# EPS.net
KiCad netlist of a schematic drawn in EAGLE
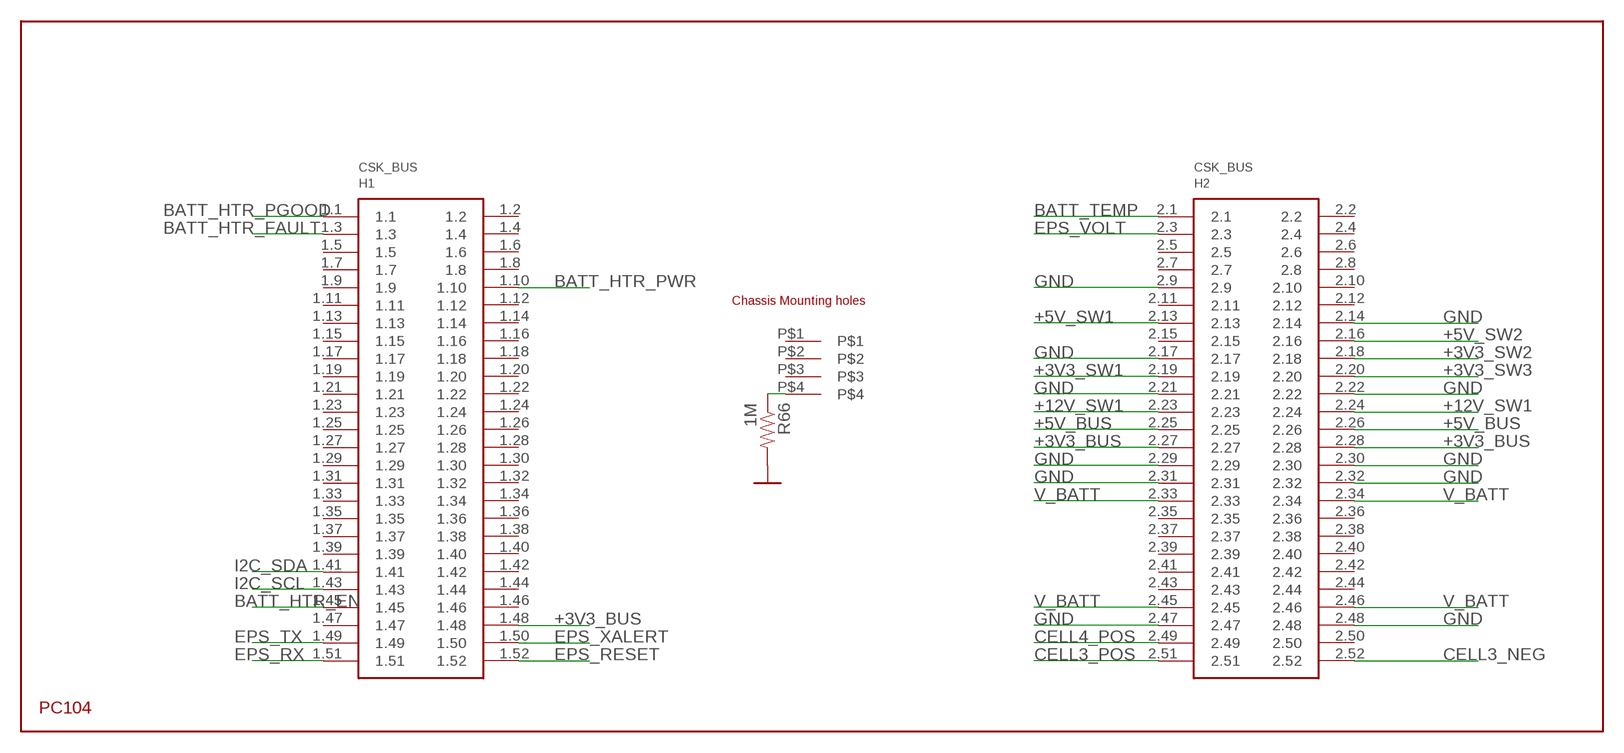
[diagram p0: schematic, sheet 1]
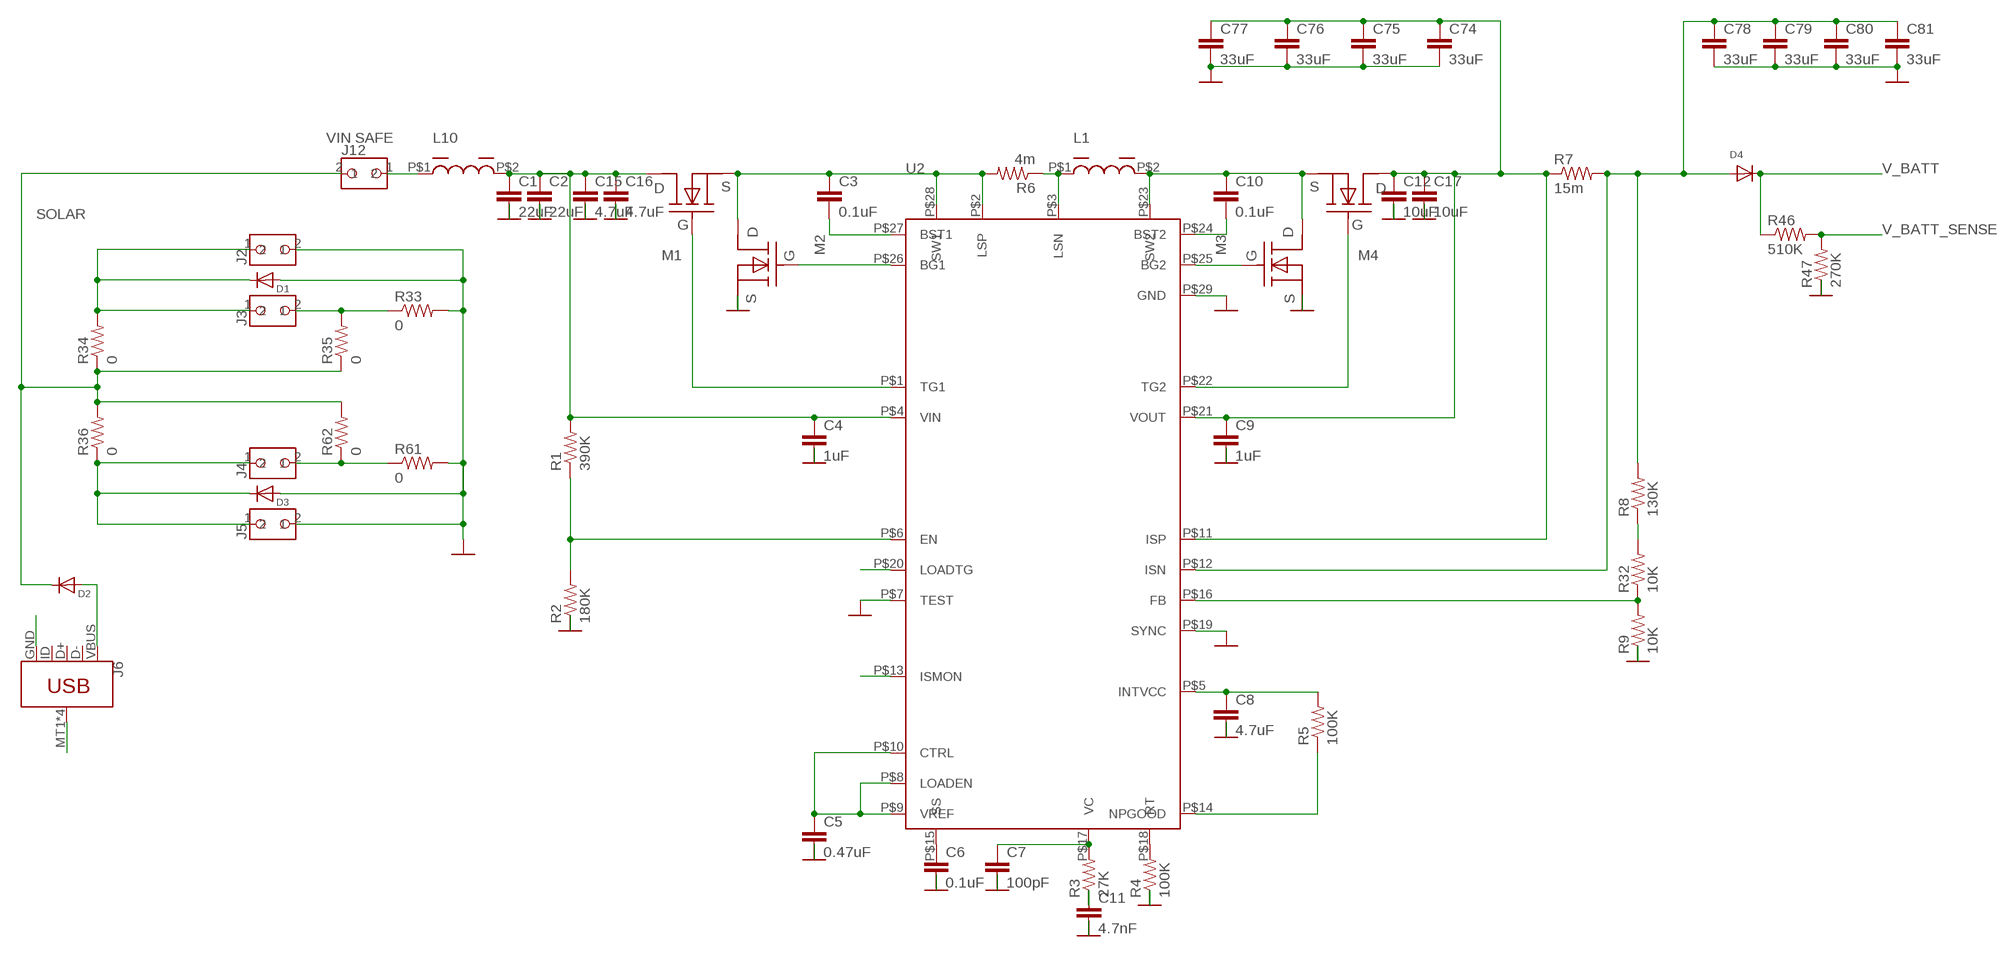
[diagram p1: schematic, sheet 2]
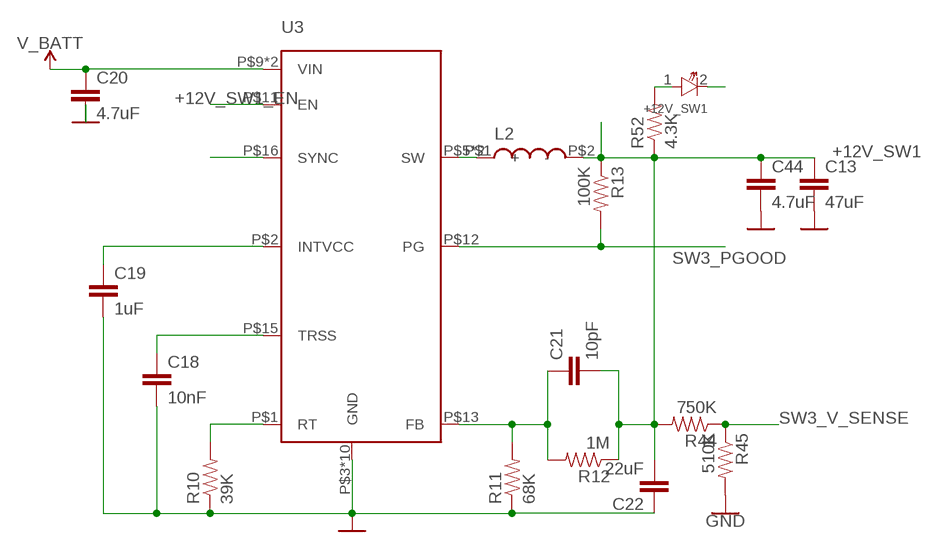
[diagram p2: schematic, sheet 3]
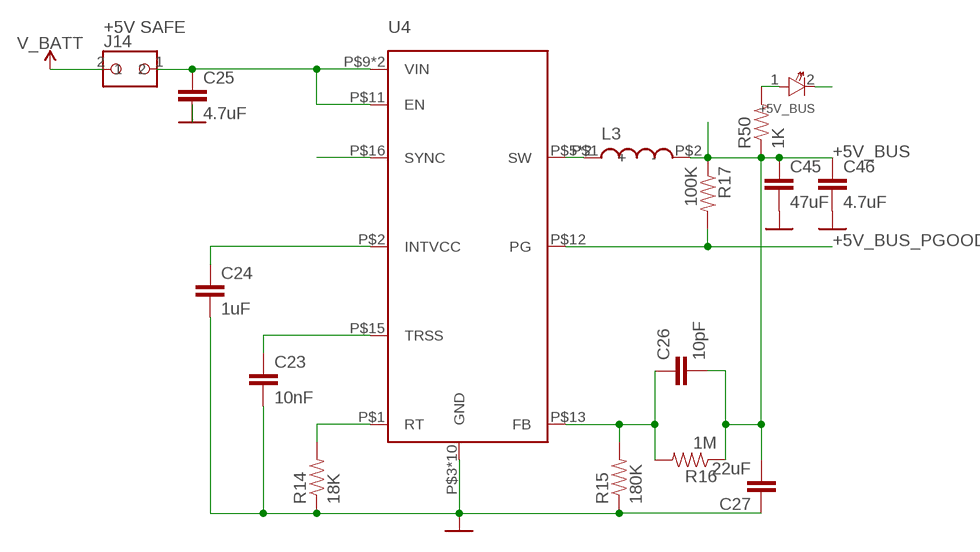
[diagram p3: schematic, sheet 4]
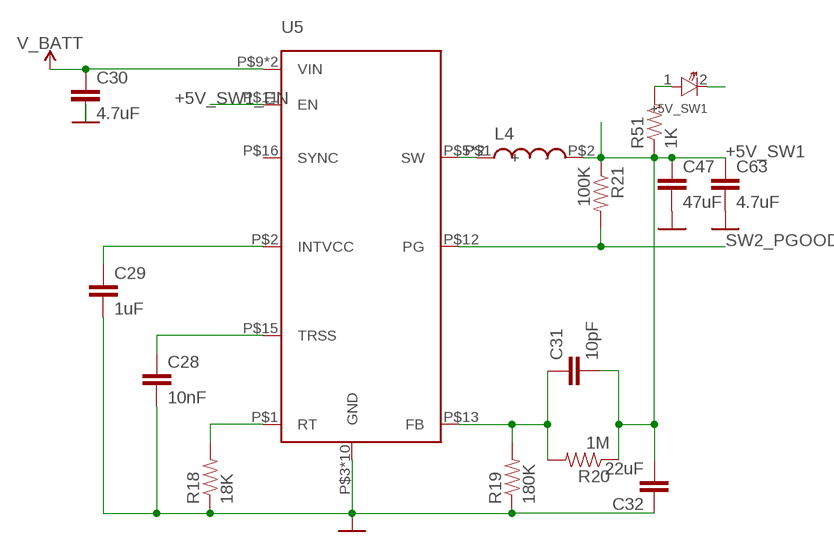
[diagram p4: schematic, sheet 5]
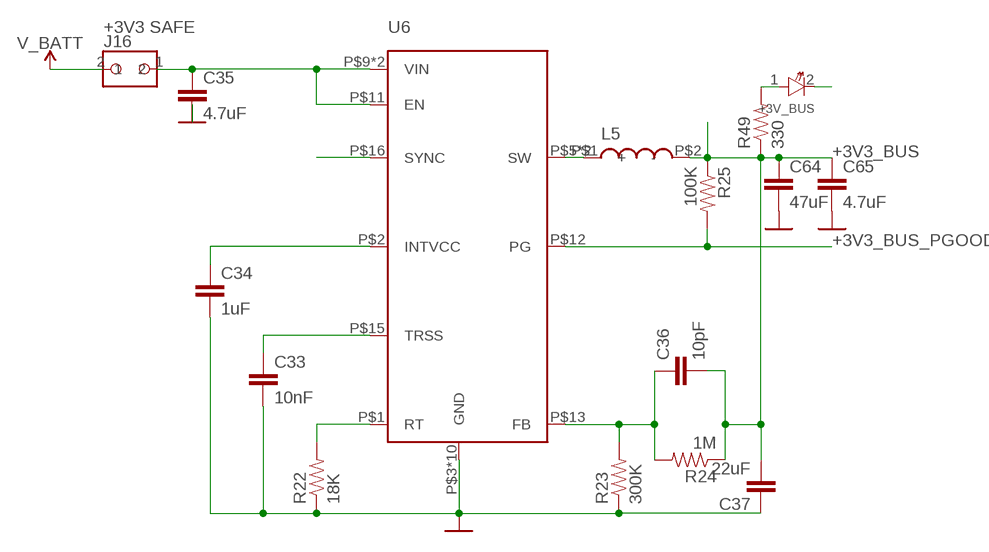
[diagram p5: schematic, sheet 6]
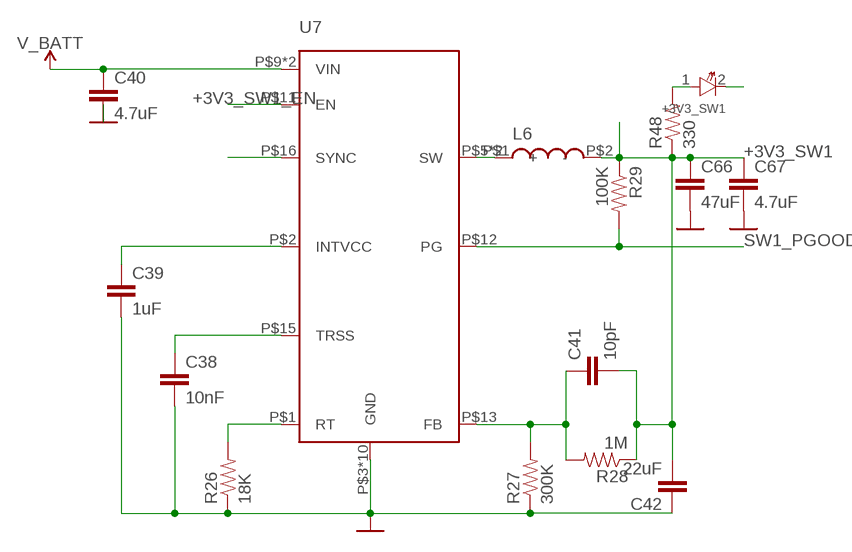
[diagram p6: schematic, sheet 7]
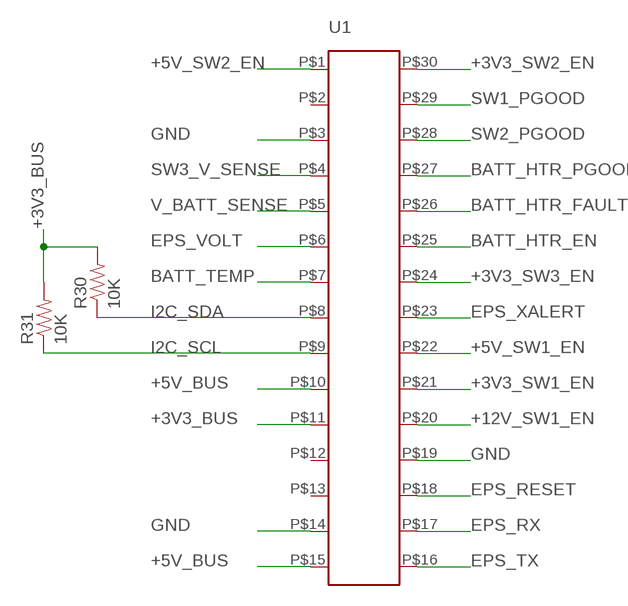
[diagram p7: schematic, sheet 8]
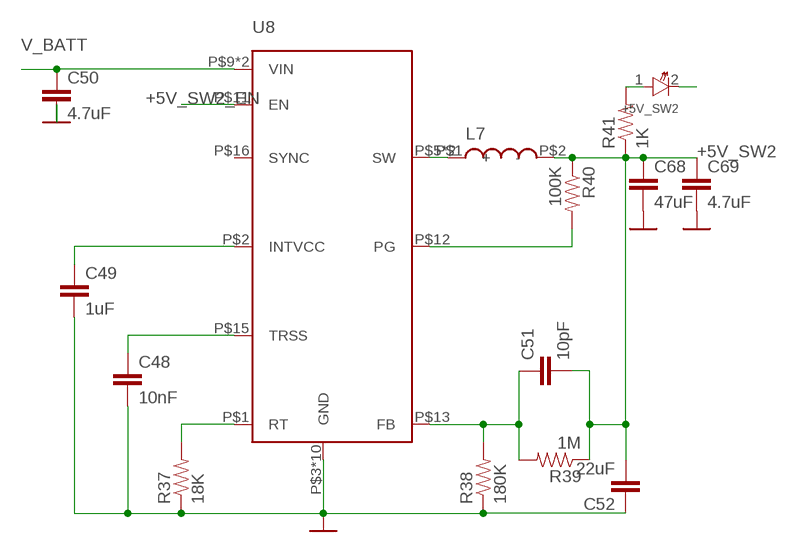
[diagram p8: schematic, sheet 9]
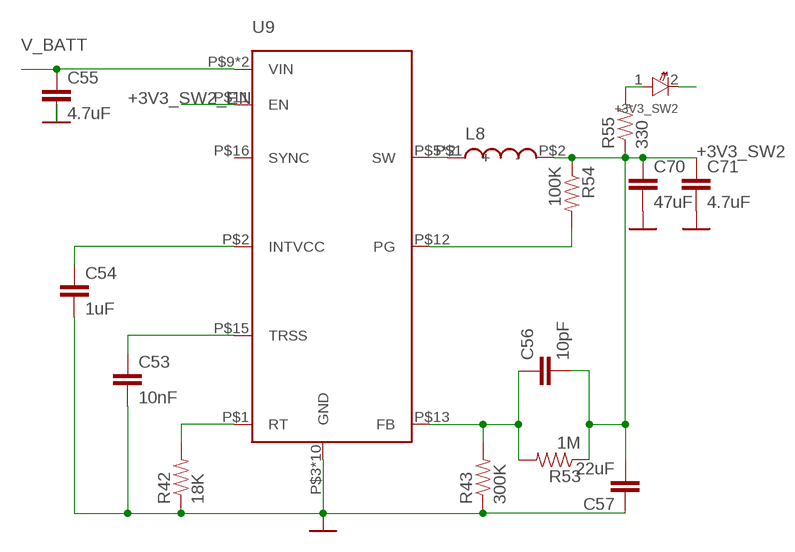
[diagram p9: schematic, sheet 10]
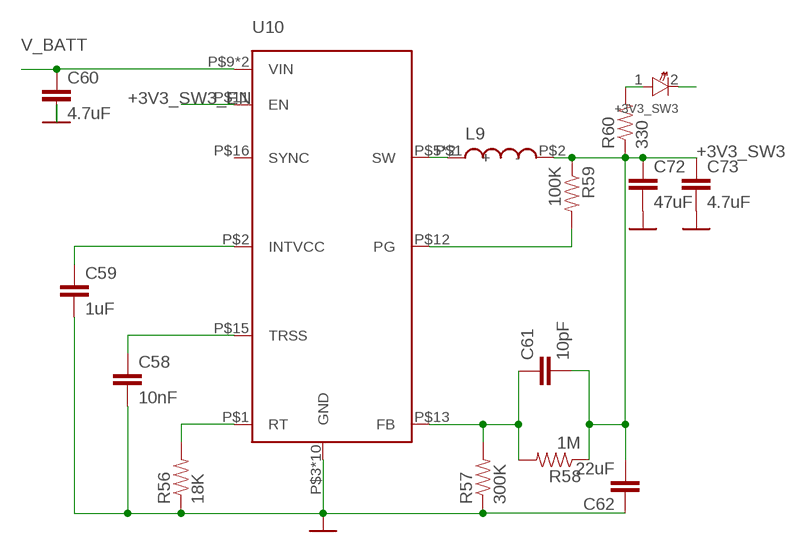
[diagram p10: schematic, sheet 11]

(export (version "E")
  (design (tool "Eeschema 10.0.6"))
  (components
    (comp (ref "R30")
      (value "10K")
      (footprint "eagle-import:0805")
      (libsource (lib "eagle-import") (part "RESISTOR0805-RES"))
    )
    (comp (ref "R31")
      (value "10K")
      (footprint "eagle-import:0805")
      (libsource (lib "eagle-import") (part "RESISTOR0805-RES"))
    )
    (comp (ref "U1")
      (value "ARDUINO_EVERY_NANO_PAD")
      (footprint "eagle-import:ARDUINO_EVERY_NANO")
      (libsource (lib "eagle-import") (part "ARDUINO_EVERY_NANO_PAD"))
    )
    (comp (ref "+3V3_SW3")
      (value "LED_0805")
      (footprint "eagle-import:LED_0805")
      (libsource (lib "eagle-import") (part "LED_0805"))
    )
    (comp (ref "C58")
      (value "10nF")
      (footprint "eagle-import:0805")
      (libsource (lib "eagle-import") (part "CAP0805"))
    )
    (comp (ref "C59")
      (value "1uF")
      (footprint "eagle-import:0805")
      (libsource (lib "eagle-import") (part "CAP0805"))
    )
    (comp (ref "C60")
      (value "4.7uF")
      (footprint "eagle-import:0805")
      (libsource (lib "eagle-import") (part "CAP0805"))
    )
    (comp (ref "C61")
      (value "10pF")
      (footprint "eagle-import:0805")
      (libsource (lib "eagle-import") (part "CAP0805"))
    )
    (comp (ref "C62")
      (value "22uF")
      (footprint "eagle-import:0805")
      (libsource (lib "eagle-import") (part "CAP0805"))
    )
    (comp (ref "C72")
      (value "47uF")
      (footprint "eagle-import:0805")
      (libsource (lib "eagle-import") (part "CAP0805"))
    )
    (comp (ref "C73")
      (value "4.7uF")
      (footprint "eagle-import:0805")
      (libsource (lib "eagle-import") (part "CAP0805"))
    )
    (comp (ref "L9")
      (value "2.2uH")
      (footprint "eagle-import:XAL4040-103ME")
      (libsource (lib "eagle-import") (part "XFL4020-222ME"))
    )
    (comp (ref "R56")
      (value "18K")
      (footprint "eagle-import:0805")
      (libsource (lib "eagle-import") (part "RESISTOR0805-RES"))
    )
    (comp (ref "R57")
      (value "300K")
      (footprint "eagle-import:0805")
      (libsource (lib "eagle-import") (part "RESISTOR0805-RES"))
    )
    (comp (ref "R58")
      (value "1M")
      (footprint "eagle-import:0805")
      (libsource (lib "eagle-import") (part "RESISTOR0805-RES"))
    )
    (comp (ref "R59")
      (value "100K")
      (footprint "eagle-import:0805")
      (libsource (lib "eagle-import") (part "RESISTOR0805-RES"))
    )
    (comp (ref "R60")
      (value "330")
      (footprint "eagle-import:0805")
      (libsource (lib "eagle-import") (part "RESISTOR0805-RES"))
    )
    (comp (ref "U10")
      (value "LT8609S")
      (footprint "eagle-import:LT8609S")
      (libsource (lib "eagle-import") (part "LT8609S"))
    )
    (comp (ref "+5V_SW1")
      (value "LED_0805")
      (footprint "eagle-import:LED_0805")
      (libsource (lib "eagle-import") (part "LED_0805"))
    )
    (comp (ref "C28")
      (value "10nF")
      (footprint "eagle-import:0805")
      (libsource (lib "eagle-import") (part "CAP0805"))
    )
    (comp (ref "C29")
      (value "1uF")
      (footprint "eagle-import:0805")
      (libsource (lib "eagle-import") (part "CAP0805"))
    )
    (comp (ref "C30")
      (value "4.7uF")
      (footprint "eagle-import:0805")
      (libsource (lib "eagle-import") (part "CAP0805"))
    )
    (comp (ref "C31")
      (value "10pF")
      (footprint "eagle-import:0805")
      (libsource (lib "eagle-import") (part "CAP0805"))
    )
    (comp (ref "C32")
      (value "22uF")
      (footprint "eagle-import:0805")
      (libsource (lib "eagle-import") (part "CAP0805"))
    )
    (comp (ref "C47")
      (value "47uF")
      (footprint "eagle-import:0805")
      (libsource (lib "eagle-import") (part "CAP0805"))
    )
    (comp (ref "C63")
      (value "4.7uF")
      (footprint "eagle-import:0805")
      (libsource (lib "eagle-import") (part "CAP0805"))
    )
    (comp (ref "L4")
      (value "2.2uH")
      (footprint "eagle-import:XAL4040-103ME")
      (libsource (lib "eagle-import") (part "XFL4020-222ME"))
    )
    (comp (ref "R18")
      (value "18K")
      (footprint "eagle-import:0805")
      (libsource (lib "eagle-import") (part "RESISTOR0805-RES"))
    )
    (comp (ref "R19")
      (value "180K")
      (footprint "eagle-import:0805")
      (libsource (lib "eagle-import") (part "RESISTOR0805-RES"))
    )
    (comp (ref "R20")
      (value "1M")
      (footprint "eagle-import:0805")
      (libsource (lib "eagle-import") (part "RESISTOR0805-RES"))
    )
    (comp (ref "R21")
      (value "100K")
      (footprint "eagle-import:0805")
      (libsource (lib "eagle-import") (part "RESISTOR0805-RES"))
    )
    (comp (ref "R51")
      (value "1K")
      (footprint "eagle-import:0805")
      (libsource (lib "eagle-import") (part "RESISTOR0805-RES"))
    )
    (comp (ref "U5")
      (value "LT8609S")
      (footprint "eagle-import:LT8609S")
      (libsource (lib "eagle-import") (part "LT8609S"))
    )
    (comp (ref "+3V3_SW1")
      (value "LED_0805")
      (footprint "eagle-import:LED_0805")
      (libsource (lib "eagle-import") (part "LED_0805"))
    )
    (comp (ref "C38")
      (value "10nF")
      (footprint "eagle-import:0805")
      (libsource (lib "eagle-import") (part "CAP0805"))
    )
    (comp (ref "C39")
      (value "1uF")
      (footprint "eagle-import:0805")
      (libsource (lib "eagle-import") (part "CAP0805"))
    )
    (comp (ref "C40")
      (value "4.7uF")
      (footprint "eagle-import:0805")
      (libsource (lib "eagle-import") (part "CAP0805"))
    )
    (comp (ref "C41")
      (value "10pF")
      (footprint "eagle-import:0805")
      (libsource (lib "eagle-import") (part "CAP0805"))
    )
    (comp (ref "C42")
      (value "22uF")
      (footprint "eagle-import:0805")
      (libsource (lib "eagle-import") (part "CAP0805"))
    )
    (comp (ref "C66")
      (value "47uF")
      (footprint "eagle-import:0805")
      (libsource (lib "eagle-import") (part "CAP0805"))
    )
    (comp (ref "C67")
      (value "4.7uF")
      (footprint "eagle-import:0805")
      (libsource (lib "eagle-import") (part "CAP0805"))
    )
    (comp (ref "L6")
      (value "2.2uH")
      (footprint "eagle-import:XAL4040-103ME")
      (libsource (lib "eagle-import") (part "XFL4020-222ME"))
    )
    (comp (ref "R26")
      (value "18K")
      (footprint "eagle-import:0805")
      (libsource (lib "eagle-import") (part "RESISTOR0805-RES"))
    )
    (comp (ref "R27")
      (value "300K")
      (footprint "eagle-import:0805")
      (libsource (lib "eagle-import") (part "RESISTOR0805-RES"))
    )
    (comp (ref "R28")
      (value "1M")
      (footprint "eagle-import:0805")
      (libsource (lib "eagle-import") (part "RESISTOR0805-RES"))
    )
    (comp (ref "R29")
      (value "100K")
      (footprint "eagle-import:0805")
      (libsource (lib "eagle-import") (part "RESISTOR0805-RES"))
    )
    (comp (ref "R48")
      (value "330")
      (footprint "eagle-import:0805")
      (libsource (lib "eagle-import") (part "RESISTOR0805-RES"))
    )
    (comp (ref "U7")
      (value "LT8609S")
      (footprint "eagle-import:LT8609S")
      (libsource (lib "eagle-import") (part "LT8609S"))
    )
    (comp (ref "+3V_BUS")
      (value "LED_0805")
      (footprint "eagle-import:LED_0805")
      (libsource (lib "eagle-import") (part "LED_0805"))
    )
    (comp (ref "C33")
      (value "10nF")
      (footprint "eagle-import:0805")
      (libsource (lib "eagle-import") (part "CAP0805"))
    )
    (comp (ref "C34")
      (value "1uF")
      (footprint "eagle-import:0805")
      (libsource (lib "eagle-import") (part "CAP0805"))
    )
    (comp (ref "C35")
      (value "4.7uF")
      (footprint "eagle-import:0805")
      (libsource (lib "eagle-import") (part "CAP0805"))
    )
    (comp (ref "C36")
      (value "10pF")
      (footprint "eagle-import:0805")
      (libsource (lib "eagle-import") (part "CAP0805"))
    )
    (comp (ref "C37")
      (value "22uF")
      (footprint "eagle-import:0805")
      (libsource (lib "eagle-import") (part "CAP0805"))
    )
    (comp (ref "C64")
      (value "47uF")
      (footprint "eagle-import:0805")
      (libsource (lib "eagle-import") (part "CAP0805"))
    )
    (comp (ref "C65")
      (value "4.7uF")
      (footprint "eagle-import:0805")
      (libsource (lib "eagle-import") (part "CAP0805"))
    )
    (comp (ref "J16")
      (value "2PIN_HEADER")
      (footprint "eagle-import:2MM_2PIN_HEADER")
      (libsource (lib "eagle-import") (part "2PIN_HEADER"))
    )
    (comp (ref "L5")
      (value "2.2uH")
      (footprint "eagle-import:XAL4040-103ME")
      (libsource (lib "eagle-import") (part "XFL4020-222ME"))
    )
    (comp (ref "R22")
      (value "18K")
      (footprint "eagle-import:0805")
      (libsource (lib "eagle-import") (part "RESISTOR0805-RES"))
    )
    (comp (ref "R23")
      (value "300K")
      (footprint "eagle-import:0805")
      (libsource (lib "eagle-import") (part "RESISTOR0805-RES"))
    )
    (comp (ref "R24")
      (value "1M")
      (footprint "eagle-import:0805")
      (libsource (lib "eagle-import") (part "RESISTOR0805-RES"))
    )
    (comp (ref "R25")
      (value "100K")
      (footprint "eagle-import:0805")
      (libsource (lib "eagle-import") (part "RESISTOR0805-RES"))
    )
    (comp (ref "R49")
      (value "330")
      (footprint "eagle-import:0805")
      (libsource (lib "eagle-import") (part "RESISTOR0805-RES"))
    )
    (comp (ref "U6")
      (value "LT8609S")
      (footprint "eagle-import:LT8609S")
      (libsource (lib "eagle-import") (part "LT8609S"))
    )
    (comp (ref "+3V3_SW2")
      (value "LED_0805")
      (footprint "eagle-import:LED_0805")
      (libsource (lib "eagle-import") (part "LED_0805"))
    )
    (comp (ref "C53")
      (value "10nF")
      (footprint "eagle-import:0805")
      (libsource (lib "eagle-import") (part "CAP0805"))
    )
    (comp (ref "C54")
      (value "1uF")
      (footprint "eagle-import:0805")
      (libsource (lib "eagle-import") (part "CAP0805"))
    )
    (comp (ref "C55")
      (value "4.7uF")
      (footprint "eagle-import:0805")
      (libsource (lib "eagle-import") (part "CAP0805"))
    )
    (comp (ref "C56")
      (value "10pF")
      (footprint "eagle-import:0805")
      (libsource (lib "eagle-import") (part "CAP0805"))
    )
    (comp (ref "C57")
      (value "22uF")
      (footprint "eagle-import:0805")
      (libsource (lib "eagle-import") (part "CAP0805"))
    )
    (comp (ref "C70")
      (value "47uF")
      (footprint "eagle-import:0805")
      (libsource (lib "eagle-import") (part "CAP0805"))
    )
    (comp (ref "C71")
      (value "4.7uF")
      (footprint "eagle-import:0805")
      (libsource (lib "eagle-import") (part "CAP0805"))
    )
    (comp (ref "L8")
      (value "2.2uH")
      (footprint "eagle-import:XAL4040-103ME")
      (libsource (lib "eagle-import") (part "XFL4020-222ME"))
    )
    (comp (ref "R42")
      (value "18K")
      (footprint "eagle-import:0805")
      (libsource (lib "eagle-import") (part "RESISTOR0805-RES"))
    )
    (comp (ref "R43")
      (value "300K")
      (footprint "eagle-import:0805")
      (libsource (lib "eagle-import") (part "RESISTOR0805-RES"))
    )
    (comp (ref "R53")
      (value "1M")
      (footprint "eagle-import:0805")
      (libsource (lib "eagle-import") (part "RESISTOR0805-RES"))
    )
    (comp (ref "R54")
      (value "100K")
      (footprint "eagle-import:0805")
      (libsource (lib "eagle-import") (part "RESISTOR0805-RES"))
    )
    (comp (ref "R55")
      (value "330")
      (footprint "eagle-import:0805")
      (libsource (lib "eagle-import") (part "RESISTOR0805-RES"))
    )
    (comp (ref "U9")
      (value "LT8609S")
      (footprint "eagle-import:LT8609S")
      (libsource (lib "eagle-import") (part "LT8609S"))
    )
    (comp (ref "H1")
      (value "PC104_WCONN")
      (footprint "eagle-import:PC104_WCONN")
      (libsource (lib "eagle-import") (part "PC104_WCONN"))
    )
    (comp (ref "R66")
      (value "1M")
      (footprint "eagle-import:0805")
      (libsource (lib "eagle-import") (part "RESISTOR0805-RES"))
    )
    (comp (ref "C1")
      (value "22uF")
      (footprint "eagle-import:0805")
      (libsource (lib "eagle-import") (part "CAP0805"))
    )
    (comp (ref "C2")
      (value "22uF")
      (footprint "eagle-import:0805")
      (libsource (lib "eagle-import") (part "CAP0805"))
    )
    (comp (ref "C3")
      (value "0.1uF")
      (footprint "eagle-import:0805")
      (libsource (lib "eagle-import") (part "CAP0805"))
    )
    (comp (ref "C4")
      (value "1uF")
      (footprint "eagle-import:0805")
      (libsource (lib "eagle-import") (part "CAP0805"))
    )
    (comp (ref "C5")
      (value "0.47uF")
      (footprint "eagle-import:0805")
      (libsource (lib "eagle-import") (part "CAP0805"))
    )
    (comp (ref "C6")
      (value "0.1uF")
      (footprint "eagle-import:0805")
      (libsource (lib "eagle-import") (part "CAP0805"))
    )
    (comp (ref "C7")
      (value "100pF")
      (footprint "eagle-import:0805")
      (libsource (lib "eagle-import") (part "CAP0805"))
    )
    (comp (ref "C8")
      (value "4.7uF")
      (footprint "eagle-import:0805")
      (libsource (lib "eagle-import") (part "CAP0805"))
    )
    (comp (ref "C9")
      (value "1uF")
      (footprint "eagle-import:0805")
      (libsource (lib "eagle-import") (part "CAP0805"))
    )
    (comp (ref "C10")
      (value "0.1uF")
      (footprint "eagle-import:0805")
      (libsource (lib "eagle-import") (part "CAP0805"))
    )
    (comp (ref "C11")
      (value "4.7nF")
      (footprint "eagle-import:0805")
      (libsource (lib "eagle-import") (part "CAP0805"))
    )
    (comp (ref "C12")
      (value "10uF")
      (footprint "eagle-import:0805")
      (libsource (lib "eagle-import") (part "CAP0805"))
    )
    (comp (ref "C15")
      (value "4.7uF")
      (footprint "eagle-import:0805")
      (libsource (lib "eagle-import") (part "CAP0805"))
    )
    (comp (ref "C16")
      (value "4.7uF")
      (footprint "eagle-import:0805")
      (libsource (lib "eagle-import") (part "CAP0805"))
    )
    (comp (ref "C17")
      (value "10uF")
      (footprint "eagle-import:0805")
      (libsource (lib "eagle-import") (part "CAP0805"))
    )
    (comp (ref "C74")
      (value "33uF")
      (footprint "eagle-import:1206")
      (libsource (lib "eagle-import") (part "CAP1206"))
    )
    (comp (ref "C75")
      (value "33uF")
      (footprint "eagle-import:1206")
      (libsource (lib "eagle-import") (part "CAP1206"))
    )
    (comp (ref "C76")
      (value "33uF")
      (footprint "eagle-import:1206")
      (libsource (lib "eagle-import") (part "CAP1206"))
    )
    (comp (ref "C77")
      (value "33uF")
      (footprint "eagle-import:1206")
      (libsource (lib "eagle-import") (part "CAP1206"))
    )
    (comp (ref "C78")
      (value "33uF")
      (footprint "eagle-import:1206")
      (libsource (lib "eagle-import") (part "CAP1206"))
    )
    (comp (ref "C79")
      (value "33uF")
      (footprint "eagle-import:1206")
      (libsource (lib "eagle-import") (part "CAP1206"))
    )
    (comp (ref "C80")
      (value "33uF")
      (footprint "eagle-import:1206")
      (libsource (lib "eagle-import") (part "CAP1206"))
    )
    (comp (ref "C81")
      (value "33uF")
      (footprint "eagle-import:1206")
      (libsource (lib "eagle-import") (part "CAP1206"))
    )
    (comp (ref "D1")
      (value "DIODE_SOD-123FL")
      (footprint "eagle-import:SOD-123FL")
      (libsource (lib "eagle-import") (part "DIODE_SOD-123FL"))
    )
    (comp (ref "D2")
      (value "DIODE_SOD-123FL")
      (footprint "eagle-import:SOD-123FL")
      (libsource (lib "eagle-import") (part "DIODE_SOD-123FL"))
    )
    (comp (ref "D3")
      (value "DIODE_SOD-123FL")
      (footprint "eagle-import:SOD-123FL")
      (libsource (lib "eagle-import") (part "DIODE_SOD-123FL"))
    )
    (comp (ref "D4")
      (value "DIODE_SOD-123FL")
      (footprint "eagle-import:SOD-123FL")
      (libsource (lib "eagle-import") (part "DIODE_SOD-123FL"))
    )
    (comp (ref "J2")
      (value "2PIN_HEADER")
      (footprint "eagle-import:2MM_2PIN_HEADER")
      (libsource (lib "eagle-import") (part "2PIN_HEADER"))
    )
    (comp (ref "J3")
      (value "2PIN_HEADER")
      (footprint "eagle-import:2MM_2PIN_HEADER")
      (libsource (lib "eagle-import") (part "2PIN_HEADER"))
    )
    (comp (ref "J4")
      (value "2PIN_HEADER")
      (footprint "eagle-import:2MM_2PIN_HEADER")
      (libsource (lib "eagle-import") (part "2PIN_HEADER"))
    )
    (comp (ref "J5")
      (value "2PIN_HEADER")
      (footprint "eagle-import:2MM_2PIN_HEADER")
      (libsource (lib "eagle-import") (part "2PIN_HEADER"))
    )
    (comp (ref "J6")
      (value "USB_MICRO-B_SMT")
      (footprint "eagle-import:USB-MICROB")
      (libsource (lib "eagle-import") (part "USB_MICRO-B_SMT"))
    )
    (comp (ref "J12")
      (value "2PIN_HEADER")
      (footprint "eagle-import:2MM_2PIN_HEADER")
      (libsource (lib "eagle-import") (part "2PIN_HEADER"))
    )
    (comp (ref "L1")
      (value "6uH")
      (footprint "eagle-import:7443551600")
      (libsource (lib "eagle-import") (part "7443551600"))
    )
    (comp (ref "L10")
      (value "6uH")
      (footprint "eagle-import:7443551600")
      (libsource (lib "eagle-import") (part "7443551600"))
    )
    (comp (ref "M1")
      (value "BSZ100N06LS3")
      (footprint "eagle-import:BSZ100N06LS3")
      (libsource (lib "eagle-import") (part "BSZ100N06LS3"))
    )
    (comp (ref "M2")
      (value "BSZ100N06LS3")
      (footprint "eagle-import:BSZ100N06LS3")
      (libsource (lib "eagle-import") (part "BSZ100N06LS3"))
    )
    (comp (ref "M3")
      (value "BSZ033NE2LS5")
      (footprint "eagle-import:BSZ100N06LS3")
      (libsource (lib "eagle-import") (part "BSZ100N06LS3"))
    )
    (comp (ref "M4")
      (value "BSZ033NE2LS5")
      (footprint "eagle-import:BSZ100N06LS3")
      (libsource (lib "eagle-import") (part "BSZ100N06LS3"))
    )
    (comp (ref "R1")
      (value "390K")
      (footprint "eagle-import:0805")
      (libsource (lib "eagle-import") (part "RESISTOR0805-RES"))
    )
    (comp (ref "R2")
      (value "180K")
      (footprint "eagle-import:0805")
      (libsource (lib "eagle-import") (part "RESISTOR0805-RES"))
    )
    (comp (ref "R3")
      (value "27K")
      (footprint "eagle-import:0805")
      (libsource (lib "eagle-import") (part "RESISTOR0805-RES"))
    )
    (comp (ref "R4")
      (value "100K")
      (footprint "eagle-import:0805")
      (libsource (lib "eagle-import") (part "RESISTOR0805-RES"))
    )
    (comp (ref "R5")
      (value "100K")
      (footprint "eagle-import:0805")
      (libsource (lib "eagle-import") (part "RESISTOR0805-RES"))
    )
    (comp (ref "R6")
      (value "4m")
      (footprint "eagle-import:0805")
      (libsource (lib "eagle-import") (part "RESISTOR0805-RES"))
    )
    (comp (ref "R7")
      (value "15m")
      (footprint "eagle-import:0805")
      (libsource (lib "eagle-import") (part "RESISTOR0805-RES"))
    )
    (comp (ref "R8")
      (value "130K")
      (footprint "eagle-import:0805")
      (libsource (lib "eagle-import") (part "RESISTOR0805-RES"))
    )
    (comp (ref "R9")
      (value "10K")
      (footprint "eagle-import:0805")
      (libsource (lib "eagle-import") (part "RESISTOR0805-RES"))
    )
    (comp (ref "R32")
      (value "10K")
      (footprint "eagle-import:0805")
      (libsource (lib "eagle-import") (part "RESISTOR0805-RES"))
    )
    (comp (ref "R33")
      (value "0")
      (footprint "eagle-import:0603-RES")
      (libsource (lib "eagle-import") (part "RESISTOR0603-RES"))
    )
    (comp (ref "R34")
      (value "0")
      (footprint "eagle-import:0603-RES")
      (libsource (lib "eagle-import") (part "RESISTOR0603-RES"))
    )
    (comp (ref "R35")
      (value "0")
      (footprint "eagle-import:0603-RES")
      (libsource (lib "eagle-import") (part "RESISTOR0603-RES"))
    )
    (comp (ref "R36")
      (value "0")
      (footprint "eagle-import:0603-RES")
      (libsource (lib "eagle-import") (part "RESISTOR0603-RES"))
    )
    (comp (ref "R46")
      (value "510K")
      (footprint "eagle-import:0805")
      (libsource (lib "eagle-import") (part "RESISTOR0805-RES"))
    )
    (comp (ref "R47")
      (value "270K")
      (footprint "eagle-import:0805")
      (libsource (lib "eagle-import") (part "RESISTOR0805-RES"))
    )
    (comp (ref "R61")
      (value "0")
      (footprint "eagle-import:0603-RES")
      (libsource (lib "eagle-import") (part "RESISTOR0603-RES"))
    )
    (comp (ref "R62")
      (value "0")
      (footprint "eagle-import:0603-RES")
      (libsource (lib "eagle-import") (part "RESISTOR0603-RES"))
    )
    (comp (ref "U2")
      (value "LT8390UFD")
      (footprint "eagle-import:LT8390UFD")
      (libsource (lib "eagle-import") (part "LT8390UFD"))
    )
    (comp (ref "+5V_SW2")
      (value "LED_0805")
      (footprint "eagle-import:LED_0805")
      (libsource (lib "eagle-import") (part "LED_0805"))
    )
    (comp (ref "C48")
      (value "10nF")
      (footprint "eagle-import:0805")
      (libsource (lib "eagle-import") (part "CAP0805"))
    )
    (comp (ref "C49")
      (value "1uF")
      (footprint "eagle-import:0805")
      (libsource (lib "eagle-import") (part "CAP0805"))
    )
    (comp (ref "C50")
      (value "4.7uF")
      (footprint "eagle-import:0805")
      (libsource (lib "eagle-import") (part "CAP0805"))
    )
    (comp (ref "C51")
      (value "10pF")
      (footprint "eagle-import:0805")
      (libsource (lib "eagle-import") (part "CAP0805"))
    )
    (comp (ref "C52")
      (value "22uF")
      (footprint "eagle-import:0805")
      (libsource (lib "eagle-import") (part "CAP0805"))
    )
    (comp (ref "C68")
      (value "47uF")
      (footprint "eagle-import:0805")
      (libsource (lib "eagle-import") (part "CAP0805"))
    )
    (comp (ref "C69")
      (value "4.7uF")
      (footprint "eagle-import:0805")
      (libsource (lib "eagle-import") (part "CAP0805"))
    )
    (comp (ref "L7")
      (value "2.2uH")
      (footprint "eagle-import:XAL4040-103ME")
      (libsource (lib "eagle-import") (part "XFL4020-222ME"))
    )
    (comp (ref "R37")
      (value "18K")
      (footprint "eagle-import:0805")
      (libsource (lib "eagle-import") (part "RESISTOR0805-RES"))
    )
    (comp (ref "R38")
      (value "180K")
      (footprint "eagle-import:0805")
      (libsource (lib "eagle-import") (part "RESISTOR0805-RES"))
    )
    (comp (ref "R39")
      (value "1M")
      (footprint "eagle-import:0805")
      (libsource (lib "eagle-import") (part "RESISTOR0805-RES"))
    )
    (comp (ref "R40")
      (value "100K")
      (footprint "eagle-import:0805")
      (libsource (lib "eagle-import") (part "RESISTOR0805-RES"))
    )
    (comp (ref "R41")
      (value "1K")
      (footprint "eagle-import:0805")
      (libsource (lib "eagle-import") (part "RESISTOR0805-RES"))
    )
    (comp (ref "U8")
      (value "LT8609S")
      (footprint "eagle-import:LT8609S")
      (libsource (lib "eagle-import") (part "LT8609S"))
    )
    (comp (ref "+5V_BUS")
      (value "LED_0805")
      (footprint "eagle-import:LED_0805")
      (libsource (lib "eagle-import") (part "LED_0805"))
    )
    (comp (ref "C23")
      (value "10nF")
      (footprint "eagle-import:0805")
      (libsource (lib "eagle-import") (part "CAP0805"))
    )
    (comp (ref "C24")
      (value "1uF")
      (footprint "eagle-import:0805")
      (libsource (lib "eagle-import") (part "CAP0805"))
    )
    (comp (ref "C25")
      (value "4.7uF")
      (footprint "eagle-import:0805")
      (libsource (lib "eagle-import") (part "CAP0805"))
    )
    (comp (ref "C26")
      (value "10pF")
      (footprint "eagle-import:0805")
      (libsource (lib "eagle-import") (part "CAP0805"))
    )
    (comp (ref "C27")
      (value "22uF")
      (footprint "eagle-import:0805")
      (libsource (lib "eagle-import") (part "CAP0805"))
    )
    (comp (ref "C45")
      (value "47uF")
      (footprint "eagle-import:0805")
      (libsource (lib "eagle-import") (part "CAP0805"))
    )
    (comp (ref "C46")
      (value "4.7uF")
      (footprint "eagle-import:0805")
      (libsource (lib "eagle-import") (part "CAP0805"))
    )
    (comp (ref "J14")
      (value "2PIN_HEADER")
      (footprint "eagle-import:2MM_2PIN_HEADER")
      (libsource (lib "eagle-import") (part "2PIN_HEADER"))
    )
    (comp (ref "L3")
      (value "2.2uH")
      (footprint "eagle-import:XAL4040-103ME")
      (libsource (lib "eagle-import") (part "XFL4020-222ME"))
    )
    (comp (ref "R14")
      (value "18K")
      (footprint "eagle-import:0805")
      (libsource (lib "eagle-import") (part "RESISTOR0805-RES"))
    )
    (comp (ref "R15")
      (value "180K")
      (footprint "eagle-import:0805")
      (libsource (lib "eagle-import") (part "RESISTOR0805-RES"))
    )
    (comp (ref "R16")
      (value "1M")
      (footprint "eagle-import:0805")
      (libsource (lib "eagle-import") (part "RESISTOR0805-RES"))
    )
    (comp (ref "R17")
      (value "100K")
      (footprint "eagle-import:0805")
      (libsource (lib "eagle-import") (part "RESISTOR0805-RES"))
    )
    (comp (ref "R50")
      (value "1K")
      (footprint "eagle-import:0805")
      (libsource (lib "eagle-import") (part "RESISTOR0805-RES"))
    )
    (comp (ref "U4")
      (value "LT8609S")
      (footprint "eagle-import:LT8609S")
      (libsource (lib "eagle-import") (part "LT8609S"))
    )
    (comp (ref "+12V_SW1")
      (value "LED_0805")
      (footprint "eagle-import:LED_0805")
      (libsource (lib "eagle-import") (part "LED_0805"))
    )
    (comp (ref "C13")
      (value "47uF")
      (footprint "eagle-import:1206")
      (libsource (lib "eagle-import") (part "CAP1206"))
    )
    (comp (ref "C18")
      (value "10nF")
      (footprint "eagle-import:0805")
      (libsource (lib "eagle-import") (part "CAP0805"))
    )
    (comp (ref "C19")
      (value "1uF")
      (footprint "eagle-import:0805")
      (libsource (lib "eagle-import") (part "CAP0805"))
    )
    (comp (ref "C20")
      (value "4.7uF")
      (footprint "eagle-import:0805")
      (libsource (lib "eagle-import") (part "CAP0805"))
    )
    (comp (ref "C21")
      (value "10pF")
      (footprint "eagle-import:0805")
      (libsource (lib "eagle-import") (part "CAP0805"))
    )
    (comp (ref "C22")
      (value "22uF")
      (footprint "eagle-import:0805")
      (libsource (lib "eagle-import") (part "CAP0805"))
    )
    (comp (ref "C44")
      (value "4.7uF")
      (footprint "eagle-import:0805")
      (libsource (lib "eagle-import") (part "CAP0805"))
    )
    (comp (ref "L2")
      (value "10uH")
      (footprint "eagle-import:XAL4040-103ME")
      (libsource (lib "eagle-import") (part "XAL4040-103ME"))
    )
    (comp (ref "R10")
      (value "39K")
      (footprint "eagle-import:0805")
      (libsource (lib "eagle-import") (part "RESISTOR0805-RES"))
    )
    (comp (ref "R11")
      (value "68K")
      (footprint "eagle-import:0805")
      (libsource (lib "eagle-import") (part "RESISTOR0805-RES"))
    )
    (comp (ref "R12")
      (value "1M")
      (footprint "eagle-import:0805")
      (libsource (lib "eagle-import") (part "RESISTOR0805-RES"))
    )
    (comp (ref "R13")
      (value "100K")
      (footprint "eagle-import:0805")
      (libsource (lib "eagle-import") (part "RESISTOR0805-RES"))
    )
    (comp (ref "R44")
      (value "750K")
      (footprint "eagle-import:0805")
      (libsource (lib "eagle-import") (part "RESISTOR0805-RES"))
    )
    (comp (ref "R45")
      (value "510K")
      (footprint "eagle-import:0805")
      (libsource (lib "eagle-import") (part "RESISTOR0805-RES"))
    )
    (comp (ref "R52")
      (value "4.3K")
      (footprint "eagle-import:0805")
      (libsource (lib "eagle-import") (part "RESISTOR0805-RES"))
    )
    (comp (ref "U3")
      (value "LT8609S")
      (footprint "eagle-import:LT8609S")
      (libsource (lib "eagle-import") (part "LT8609S"))
    )
  )
  (nets
    (net (code "1") (name "+3V3_BUS") (class "Default")
      (node (ref "C36") (pin "2") (pinfunction "2_2") (pintype "passive"))
      (node (ref "C37") (pin "2") (pinfunction "2_2") (pintype "passive"))
      (node (ref "C64") (pin "1") (pinfunction "1_1") (pintype "passive"))
      (node (ref "C65") (pin "1") (pinfunction "1_1") (pintype "passive"))
      (node (ref "H1") (pin "1.48") (pinfunction "1.48_1.48") (pintype "bidirectional"))
      (node (ref "H1") (pin "2.27") (pinfunction "2.27_2.27") (pintype "bidirectional"))
      (node (ref "H1") (pin "2.28") (pinfunction "2.28_2.28") (pintype "bidirectional"))
      (node (ref "L5") (pin "P$2") (pinfunction "-_P$2") (pintype "bidirectional"))
      (node (ref "R24") (pin "1") (pinfunction "1_1") (pintype "passive"))
      (node (ref "R25") (pin "1") (pinfunction "1_1") (pintype "passive"))
      (node (ref "R30") (pin "2") (pinfunction "2_2") (pintype "passive"))
      (node (ref "R31") (pin "2") (pinfunction "2_2") (pintype "passive"))
      (node (ref "R49") (pin "1") (pinfunction "1_1") (pintype "passive"))
      (node (ref "U1") (pin "P$11") (pinfunction "P$11_P$11") (pintype "bidirectional"))
    )
    (net (code "2") (name "+3V3_BUS_PGOOD") (class "Default")
      (node (ref "R25") (pin "2") (pinfunction "2_2") (pintype "passive"))
      (node (ref "U6") (pin "P$12") (pinfunction "PG_P$12") (pintype "input"))
    )
    (net (code "3") (name "+3V3_SW1") (class "Default")
      (node (ref "C41") (pin "2") (pinfunction "2_2") (pintype "passive"))
      (node (ref "C42") (pin "2") (pinfunction "2_2") (pintype "passive"))
      (node (ref "C66") (pin "1") (pinfunction "1_1") (pintype "passive"))
      (node (ref "C67") (pin "1") (pinfunction "1_1") (pintype "passive"))
      (node (ref "H1") (pin "2.19") (pinfunction "2.19_2.19") (pintype "bidirectional"))
      (node (ref "L6") (pin "P$2") (pinfunction "-_P$2") (pintype "bidirectional"))
      (node (ref "R28") (pin "1") (pinfunction "1_1") (pintype "passive"))
      (node (ref "R29") (pin "1") (pinfunction "1_1") (pintype "passive"))
      (node (ref "R48") (pin "1") (pinfunction "1_1") (pintype "passive"))
    )
    (net (code "4") (name "+3V3_SW1_EN") (class "Default")
      (node (ref "U1") (pin "P$21") (pinfunction "P$21_P$21") (pintype "bidirectional"))
      (node (ref "U7") (pin "P$11") (pinfunction "EN_P$11") (pintype "input"))
    )
    (net (code "5") (name "+3V3_SW2") (class "Default")
      (node (ref "C56") (pin "2") (pinfunction "2_2") (pintype "passive"))
      (node (ref "C57") (pin "2") (pinfunction "2_2") (pintype "passive"))
      (node (ref "C70") (pin "1") (pinfunction "1_1") (pintype "passive"))
      (node (ref "C71") (pin "1") (pinfunction "1_1") (pintype "passive"))
      (node (ref "H1") (pin "2.18") (pinfunction "2.18_2.18") (pintype "bidirectional"))
      (node (ref "L8") (pin "P$2") (pinfunction "-_P$2") (pintype "bidirectional"))
      (node (ref "R53") (pin "1") (pinfunction "1_1") (pintype "passive"))
      (node (ref "R54") (pin "1") (pinfunction "1_1") (pintype "passive"))
      (node (ref "R55") (pin "1") (pinfunction "1_1") (pintype "passive"))
    )
    (net (code "6") (name "+3V3_SW2_EN") (class "Default")
      (node (ref "U1") (pin "P$30") (pinfunction "P$30_P$30") (pintype "bidirectional"))
      (node (ref "U9") (pin "P$11") (pinfunction "EN_P$11") (pintype "input"))
    )
    (net (code "7") (name "+3V3_SW3") (class "Default")
      (node (ref "C61") (pin "2") (pinfunction "2_2") (pintype "passive"))
      (node (ref "C62") (pin "2") (pinfunction "2_2") (pintype "passive"))
      (node (ref "C72") (pin "1") (pinfunction "1_1") (pintype "passive"))
      (node (ref "C73") (pin "1") (pinfunction "1_1") (pintype "passive"))
      (node (ref "H1") (pin "2.20") (pinfunction "2.20_2.20") (pintype "bidirectional"))
      (node (ref "L9") (pin "P$2") (pinfunction "-_P$2") (pintype "bidirectional"))
      (node (ref "R58") (pin "1") (pinfunction "1_1") (pintype "passive"))
      (node (ref "R59") (pin "1") (pinfunction "1_1") (pintype "passive"))
      (node (ref "R60") (pin "1") (pinfunction "1_1") (pintype "passive"))
    )
    (net (code "8") (name "+3V3_SW3_EN") (class "Default")
      (node (ref "U1") (pin "P$24") (pinfunction "P$24_P$24") (pintype "bidirectional"))
      (node (ref "U10") (pin "P$11") (pinfunction "EN_P$11") (pintype "input"))
    )
    (net (code "9") (name "+5V_BUS") (class "Default")
      (node (ref "C26") (pin "2") (pinfunction "2_2") (pintype "passive"))
      (node (ref "C27") (pin "2") (pinfunction "2_2") (pintype "passive"))
      (node (ref "C45") (pin "1") (pinfunction "1_1") (pintype "passive"))
      (node (ref "C46") (pin "1") (pinfunction "1_1") (pintype "passive"))
      (node (ref "H1") (pin "2.25") (pinfunction "2.25_2.25") (pintype "bidirectional"))
      (node (ref "H1") (pin "2.26") (pinfunction "2.26_2.26") (pintype "bidirectional"))
      (node (ref "L3") (pin "P$2") (pinfunction "-_P$2") (pintype "bidirectional"))
      (node (ref "R16") (pin "1") (pinfunction "1_1") (pintype "passive"))
      (node (ref "R17") (pin "1") (pinfunction "1_1") (pintype "passive"))
      (node (ref "R50") (pin "1") (pinfunction "1_1") (pintype "passive"))
      (node (ref "U1") (pin "P$10") (pinfunction "P$10_P$10") (pintype "bidirectional"))
      (node (ref "U1") (pin "P$15") (pinfunction "P$15_P$15") (pintype "bidirectional"))
    )
    (net (code "10") (name "+5V_BUS_PGOOD") (class "Default")
      (node (ref "R17") (pin "2") (pinfunction "2_2") (pintype "passive"))
      (node (ref "U4") (pin "P$12") (pinfunction "PG_P$12") (pintype "input"))
    )
    (net (code "11") (name "+5V_SW1") (class "Default")
      (node (ref "C31") (pin "2") (pinfunction "2_2") (pintype "passive"))
      (node (ref "C32") (pin "2") (pinfunction "2_2") (pintype "passive"))
      (node (ref "C47") (pin "1") (pinfunction "1_1") (pintype "passive"))
      (node (ref "C63") (pin "1") (pinfunction "1_1") (pintype "passive"))
      (node (ref "H1") (pin "2.13") (pinfunction "2.13_2.13") (pintype "bidirectional"))
      (node (ref "L4") (pin "P$2") (pinfunction "-_P$2") (pintype "bidirectional"))
      (node (ref "R20") (pin "1") (pinfunction "1_1") (pintype "passive"))
      (node (ref "R21") (pin "1") (pinfunction "1_1") (pintype "passive"))
      (node (ref "R51") (pin "1") (pinfunction "1_1") (pintype "passive"))
    )
    (net (code "12") (name "+5V_SW1_EN") (class "Default")
      (node (ref "U1") (pin "P$22") (pinfunction "P$22_P$22") (pintype "bidirectional"))
      (node (ref "U5") (pin "P$11") (pinfunction "EN_P$11") (pintype "input"))
    )
    (net (code "13") (name "+5V_SW2") (class "Default")
      (node (ref "C51") (pin "2") (pinfunction "2_2") (pintype "passive"))
      (node (ref "C52") (pin "2") (pinfunction "2_2") (pintype "passive"))
      (node (ref "C68") (pin "1") (pinfunction "1_1") (pintype "passive"))
      (node (ref "C69") (pin "1") (pinfunction "1_1") (pintype "passive"))
      (node (ref "H1") (pin "2.16") (pinfunction "2.16_2.16") (pintype "bidirectional"))
      (node (ref "L7") (pin "P$2") (pinfunction "-_P$2") (pintype "bidirectional"))
      (node (ref "R39") (pin "1") (pinfunction "1_1") (pintype "passive"))
      (node (ref "R40") (pin "1") (pinfunction "1_1") (pintype "passive"))
      (node (ref "R41") (pin "1") (pinfunction "1_1") (pintype "passive"))
    )
    (net (code "14") (name "+5V_SW2_EN") (class "Default")
      (node (ref "U1") (pin "P$1") (pinfunction "P$1_P$1") (pintype "bidirectional"))
      (node (ref "U8") (pin "P$11") (pinfunction "EN_P$11") (pintype "input"))
    )
    (net (code "15") (name "+12V_SW1") (class "Default")
      (node (ref "C13") (pin "1") (pinfunction "1_1") (pintype "passive"))
      (node (ref "C21") (pin "2") (pinfunction "2_2") (pintype "passive"))
      (node (ref "C22") (pin "2") (pinfunction "2_2") (pintype "passive"))
      (node (ref "C44") (pin "1") (pinfunction "1_1") (pintype "passive"))
      (node (ref "H1") (pin "2.23") (pinfunction "2.23_2.23") (pintype "bidirectional"))
      (node (ref "H1") (pin "2.24") (pinfunction "2.24_2.24") (pintype "bidirectional"))
      (node (ref "L2") (pin "P$2") (pinfunction "-_P$2") (pintype "bidirectional"))
      (node (ref "R12") (pin "1") (pinfunction "1_1") (pintype "passive"))
      (node (ref "R13") (pin "1") (pinfunction "1_1") (pintype "passive"))
      (node (ref "R44") (pin "2") (pinfunction "2_2") (pintype "passive"))
      (node (ref "R52") (pin "1") (pinfunction "1_1") (pintype "passive"))
    )
    (net (code "16") (name "+12V_SW1_EN") (class "Default")
      (node (ref "U1") (pin "P$20") (pinfunction "P$20_P$20") (pintype "bidirectional"))
      (node (ref "U3") (pin "P$11") (pinfunction "EN_P$11") (pintype "input"))
    )
    (net (code "17") (name "BATT_HTR_EN") (class "Default")
      (node (ref "H1") (pin "1.45") (pinfunction "1.45_1.45") (pintype "bidirectional"))
      (node (ref "U1") (pin "P$25") (pinfunction "P$25_P$25") (pintype "bidirectional"))
    )
    (net (code "18") (name "BATT_HTR_FAULT") (class "Default")
      (node (ref "H1") (pin "1.3") (pinfunction "1.3_1.3") (pintype "bidirectional"))
      (node (ref "U1") (pin "P$26") (pinfunction "P$26_P$26") (pintype "bidirectional"))
    )
    (net (code "19") (name "BATT_HTR_PGOOD") (class "Default")
      (node (ref "H1") (pin "1.1") (pinfunction "1.1_1.1") (pintype "bidirectional"))
      (node (ref "U1") (pin "P$27") (pinfunction "P$27_P$27") (pintype "bidirectional"))
    )
    (net (code "20") (name "BATT_HTR_PWR") (class "Default")
      (node (ref "H1") (pin "1.10") (pinfunction "1.10_1.10") (pintype "bidirectional"))
    )
    (net (code "21") (name "BATT_TEMP") (class "Default")
      (node (ref "H1") (pin "2.1") (pinfunction "2.1_2.1") (pintype "bidirectional"))
      (node (ref "U1") (pin "P$7") (pinfunction "P$7_P$7") (pintype "bidirectional"))
    )
    (net (code "22") (name "CELL3_NEG") (class "Default")
      (node (ref "H1") (pin "2.52") (pinfunction "2.52_2.52") (pintype "bidirectional"))
    )
    (net (code "23") (name "CELL3_POS") (class "Default")
      (node (ref "H1") (pin "2.51") (pinfunction "2.51_2.51") (pintype "bidirectional"))
    )
    (net (code "24") (name "CELL4_POS") (class "Default")
      (node (ref "H1") (pin "2.49") (pinfunction "2.49_2.49") (pintype "bidirectional"))
    )
    (net (code "25") (name "EPS_RESET") (class "Default")
      (node (ref "H1") (pin "1.52") (pinfunction "1.52_1.52") (pintype "bidirectional"))
      (node (ref "U1") (pin "P$18") (pinfunction "P$18_P$18") (pintype "bidirectional"))
    )
    (net (code "26") (name "EPS_RX") (class "Default")
      (node (ref "H1") (pin "1.51") (pinfunction "1.51_1.51") (pintype "bidirectional"))
      (node (ref "U1") (pin "P$17") (pinfunction "P$17_P$17") (pintype "bidirectional"))
    )
    (net (code "27") (name "EPS_TX") (class "Default")
      (node (ref "H1") (pin "1.49") (pinfunction "1.49_1.49") (pintype "bidirectional"))
      (node (ref "U1") (pin "P$16") (pinfunction "P$16_P$16") (pintype "bidirectional"))
    )
    (net (code "28") (name "EPS_VOLT") (class "Default")
      (node (ref "H1") (pin "2.3") (pinfunction "2.3_2.3") (pintype "bidirectional"))
      (node (ref "U1") (pin "P$6") (pinfunction "P$6_P$6") (pintype "bidirectional"))
    )
    (net (code "29") (name "EPS_XALERT") (class "Default")
      (node (ref "H1") (pin "1.50") (pinfunction "1.50_1.50") (pintype "bidirectional"))
      (node (ref "U1") (pin "P$23") (pinfunction "P$23_P$23") (pintype "bidirectional"))
    )
    (net (code "30") (name "GND") (class "Default")
      (node (ref "+12V_SW1") (pin "2") (pinfunction "2_2") (pintype "bidirectional"))
      (node (ref "+3V3_SW1") (pin "2") (pinfunction "2_2") (pintype "bidirectional"))
      (node (ref "+3V3_SW2") (pin "2") (pinfunction "2_2") (pintype "bidirectional"))
      (node (ref "+3V3_SW3") (pin "2") (pinfunction "2_2") (pintype "bidirectional"))
      (node (ref "+3V_BUS") (pin "2") (pinfunction "2_2") (pintype "bidirectional"))
      (node (ref "+5V_BUS") (pin "2") (pinfunction "2_2") (pintype "bidirectional"))
      (node (ref "+5V_SW1") (pin "2") (pinfunction "2_2") (pintype "bidirectional"))
      (node (ref "+5V_SW2") (pin "2") (pinfunction "2_2") (pintype "bidirectional"))
      (node (ref "C1") (pin "2") (pinfunction "2_2") (pintype "passive"))
      (node (ref "C11") (pin "2") (pinfunction "2_2") (pintype "passive"))
      (node (ref "C12") (pin "2") (pinfunction "2_2") (pintype "passive"))
      (node (ref "C13") (pin "2") (pinfunction "2_2") (pintype "passive"))
      (node (ref "C15") (pin "2") (pinfunction "2_2") (pintype "passive"))
      (node (ref "C16") (pin "2") (pinfunction "2_2") (pintype "passive"))
      (node (ref "C17") (pin "2") (pinfunction "2_2") (pintype "passive"))
      (node (ref "C18") (pin "2") (pinfunction "2_2") (pintype "passive"))
      (node (ref "C19") (pin "2") (pinfunction "2_2") (pintype "passive"))
      (node (ref "C2") (pin "2") (pinfunction "2_2") (pintype "passive"))
      (node (ref "C20") (pin "2") (pinfunction "2_2") (pintype "passive"))
      (node (ref "C22") (pin "1") (pinfunction "1_1") (pintype "passive"))
      (node (ref "C23") (pin "2") (pinfunction "2_2") (pintype "passive"))
      (node (ref "C24") (pin "2") (pinfunction "2_2") (pintype "passive"))
      (node (ref "C25") (pin "2") (pinfunction "2_2") (pintype "passive"))
      (node (ref "C27") (pin "1") (pinfunction "1_1") (pintype "passive"))
      (node (ref "C28") (pin "2") (pinfunction "2_2") (pintype "passive"))
      (node (ref "C29") (pin "2") (pinfunction "2_2") (pintype "passive"))
      (node (ref "C30") (pin "2") (pinfunction "2_2") (pintype "passive"))
      (node (ref "C32") (pin "1") (pinfunction "1_1") (pintype "passive"))
      (node (ref "C33") (pin "2") (pinfunction "2_2") (pintype "passive"))
      (node (ref "C34") (pin "2") (pinfunction "2_2") (pintype "passive"))
      (node (ref "C35") (pin "2") (pinfunction "2_2") (pintype "passive"))
      (node (ref "C37") (pin "1") (pinfunction "1_1") (pintype "passive"))
      (node (ref "C38") (pin "2") (pinfunction "2_2") (pintype "passive"))
      (node (ref "C39") (pin "2") (pinfunction "2_2") (pintype "passive"))
      (node (ref "C4") (pin "2") (pinfunction "2_2") (pintype "passive"))
      (node (ref "C40") (pin "2") (pinfunction "2_2") (pintype "passive"))
      (node (ref "C42") (pin "1") (pinfunction "1_1") (pintype "passive"))
      (node (ref "C44") (pin "2") (pinfunction "2_2") (pintype "passive"))
      (node (ref "C45") (pin "2") (pinfunction "2_2") (pintype "passive"))
      (node (ref "C46") (pin "2") (pinfunction "2_2") (pintype "passive"))
      (node (ref "C47") (pin "2") (pinfunction "2_2") (pintype "passive"))
      (node (ref "C48") (pin "2") (pinfunction "2_2") (pintype "passive"))
      (node (ref "C49") (pin "2") (pinfunction "2_2") (pintype "passive"))
      (node (ref "C5") (pin "2") (pinfunction "2_2") (pintype "passive"))
      (node (ref "C50") (pin "2") (pinfunction "2_2") (pintype "passive"))
      (node (ref "C52") (pin "1") (pinfunction "1_1") (pintype "passive"))
      (node (ref "C53") (pin "2") (pinfunction "2_2") (pintype "passive"))
      (node (ref "C54") (pin "2") (pinfunction "2_2") (pintype "passive"))
      (node (ref "C55") (pin "2") (pinfunction "2_2") (pintype "passive"))
      (node (ref "C57") (pin "1") (pinfunction "1_1") (pintype "passive"))
      (node (ref "C58") (pin "2") (pinfunction "2_2") (pintype "passive"))
      (node (ref "C59") (pin "2") (pinfunction "2_2") (pintype "passive"))
      (node (ref "C6") (pin "2") (pinfunction "2_2") (pintype "passive"))
      (node (ref "C60") (pin "2") (pinfunction "2_2") (pintype "passive"))
      (node (ref "C62") (pin "1") (pinfunction "1_1") (pintype "passive"))
      (node (ref "C63") (pin "2") (pinfunction "2_2") (pintype "passive"))
      (node (ref "C64") (pin "2") (pinfunction "2_2") (pintype "passive"))
      (node (ref "C65") (pin "2") (pinfunction "2_2") (pintype "passive"))
      (node (ref "C66") (pin "2") (pinfunction "2_2") (pintype "passive"))
      (node (ref "C67") (pin "2") (pinfunction "2_2") (pintype "passive"))
      (node (ref "C68") (pin "2") (pinfunction "2_2") (pintype "passive"))
      (node (ref "C69") (pin "2") (pinfunction "2_2") (pintype "passive"))
      (node (ref "C7") (pin "2") (pinfunction "2_2") (pintype "passive"))
      (node (ref "C70") (pin "2") (pinfunction "2_2") (pintype "passive"))
      (node (ref "C71") (pin "2") (pinfunction "2_2") (pintype "passive"))
      (node (ref "C72") (pin "2") (pinfunction "2_2") (pintype "passive"))
      (node (ref "C73") (pin "2") (pinfunction "2_2") (pintype "passive"))
      (node (ref "C74") (pin "2") (pinfunction "2_2") (pintype "passive"))
      (node (ref "C75") (pin "2") (pinfunction "2_2") (pintype "passive"))
      (node (ref "C76") (pin "2") (pinfunction "2_2") (pintype "passive"))
      (node (ref "C77") (pin "2") (pinfunction "2_2") (pintype "passive"))
      (node (ref "C78") (pin "2") (pinfunction "2_2") (pintype "passive"))
      (node (ref "C79") (pin "2") (pinfunction "2_2") (pintype "passive"))
      (node (ref "C8") (pin "2") (pinfunction "2_2") (pintype "passive"))
      (node (ref "C80") (pin "2") (pinfunction "2_2") (pintype "passive"))
      (node (ref "C81") (pin "2") (pinfunction "2_2") (pintype "passive"))
      (node (ref "C9") (pin "2") (pinfunction "2_2") (pintype "passive"))
      (node (ref "D1") (pin "A") (pinfunction "A_A") (pintype "passive"))
      (node (ref "D3") (pin "A") (pinfunction "A_A") (pintype "passive"))
      (node (ref "H1") (pin "2.14") (pinfunction "2.14_2.14") (pintype "bidirectional"))
      (node (ref "H1") (pin "2.17") (pinfunction "2.17_2.17") (pintype "bidirectional"))
      (node (ref "H1") (pin "2.21") (pinfunction "2.21_2.21") (pintype "bidirectional"))
      (node (ref "H1") (pin "2.22") (pinfunction "2.22_2.22") (pintype "bidirectional"))
      (node (ref "H1") (pin "2.29") (pinfunction "2.29_2.29") (pintype "bidirectional"))
      (node (ref "H1") (pin "2.30") (pinfunction "2.30_2.30") (pintype "bidirectional"))
      (node (ref "H1") (pin "2.31") (pinfunction "2.31_2.31") (pintype "bidirectional"))
      (node (ref "H1") (pin "2.32") (pinfunction "2.32_2.32") (pintype "bidirectional"))
      (node (ref "H1") (pin "2.47") (pinfunction "2.47_2.47") (pintype "bidirectional"))
      (node (ref "H1") (pin "2.48") (pinfunction "2.48_2.48") (pintype "bidirectional"))
      (node (ref "H1") (pin "2.9") (pinfunction "2.9_2.9") (pintype "bidirectional"))
      (node (ref "J2") (pin "2") (pinfunction "2_2") (pintype "bidirectional"))
      (node (ref "J5") (pin "2") (pinfunction "2_2") (pintype "bidirectional"))
      (node (ref "J6") (pin "GND") (pinfunction "GND_GND") (pintype "power_in"))
      (node (ref "J6") (pin "MT1") (pinfunction "SHIELD_MT1") (pintype "bidirectional"))
      (node (ref "J6") (pin "MT2") (pinfunction "SHIELD_MT2") (pintype "bidirectional"))
      (node (ref "J6") (pin "P$1") (pinfunction "SHIELD_P$1") (pintype "bidirectional"))
      (node (ref "J6") (pin "P$2") (pinfunction "SHIELD_P$2") (pintype "bidirectional"))
      (node (ref "M2") (pin "P$2") (pinfunction "S_P$2") (pintype "input"))
      (node (ref "M2") (pin "P$3") (pinfunction "S_P$3") (pintype "input"))
      (node (ref "M2") (pin "P$4") (pinfunction "S_P$4") (pintype "input"))
      (node (ref "M3") (pin "P$2") (pinfunction "S_P$2") (pintype "input"))
      (node (ref "M3") (pin "P$3") (pinfunction "S_P$3") (pintype "input"))
      (node (ref "M3") (pin "P$4") (pinfunction "S_P$4") (pintype "input"))
      (node (ref "R10") (pin "1") (pinfunction "1_1") (pintype "passive"))
      (node (ref "R11") (pin "1") (pinfunction "1_1") (pintype "passive"))
      (node (ref "R14") (pin "1") (pinfunction "1_1") (pintype "passive"))
      (node (ref "R15") (pin "1") (pinfunction "1_1") (pintype "passive"))
      (node (ref "R18") (pin "1") (pinfunction "1_1") (pintype "passive"))
      (node (ref "R19") (pin "1") (pinfunction "1_1") (pintype "passive"))
      (node (ref "R2") (pin "1") (pinfunction "1_1") (pintype "passive"))
      (node (ref "R22") (pin "1") (pinfunction "1_1") (pintype "passive"))
      (node (ref "R23") (pin "1") (pinfunction "1_1") (pintype "passive"))
      (node (ref "R26") (pin "1") (pinfunction "1_1") (pintype "passive"))
      (node (ref "R27") (pin "1") (pinfunction "1_1") (pintype "passive"))
      (node (ref "R33") (pin "2") (pinfunction "2_2") (pintype "passive"))
      (node (ref "R37") (pin "1") (pinfunction "1_1") (pintype "passive"))
      (node (ref "R38") (pin "1") (pinfunction "1_1") (pintype "passive"))
      (node (ref "R4") (pin "1") (pinfunction "1_1") (pintype "passive"))
      (node (ref "R42") (pin "1") (pinfunction "1_1") (pintype "passive"))
      (node (ref "R43") (pin "1") (pinfunction "1_1") (pintype "passive"))
      (node (ref "R45") (pin "2") (pinfunction "2_2") (pintype "passive"))
      (node (ref "R47") (pin "1") (pinfunction "1_1") (pintype "passive"))
      (node (ref "R56") (pin "1") (pinfunction "1_1") (pintype "passive"))
      (node (ref "R57") (pin "1") (pinfunction "1_1") (pintype "passive"))
      (node (ref "R61") (pin "2") (pinfunction "2_2") (pintype "passive"))
      (node (ref "R66") (pin "2") (pinfunction "2_2") (pintype "passive"))
      (node (ref "R9") (pin "1") (pinfunction "1_1") (pintype "passive"))
      (node (ref "U1") (pin "P$14") (pinfunction "P$14_P$14") (pintype "bidirectional"))
      (node (ref "U1") (pin "P$19") (pinfunction "P$19_P$19") (pintype "bidirectional"))
      (node (ref "U1") (pin "P$3") (pinfunction "P$3_P$3") (pintype "bidirectional"))
      (node (ref "U10") (pin "P$14") (pinfunction "GND_P$14") (pintype "output"))
      (node (ref "U10") (pin "P$17") (pinfunction "GND_P$17") (pintype "output"))
      (node (ref "U10") (pin "P$18") (pinfunction "GND_P$18") (pintype "output"))
      (node (ref "U10") (pin "P$19") (pinfunction "GND_P$19") (pintype "output"))
      (node (ref "U10") (pin "P$20") (pinfunction "GND_P$20") (pintype "output"))
      (node (ref "U10") (pin "P$21") (pinfunction "GND_P$21") (pintype "output"))
      (node (ref "U10") (pin "P$3") (pinfunction "GND_P$3") (pintype "output"))
      (node (ref "U10") (pin "P$4") (pinfunction "GND_P$4") (pintype "output"))
      (node (ref "U10") (pin "P$7") (pinfunction "GND_P$7") (pintype "output"))
      (node (ref "U10") (pin "P$8") (pinfunction "GND_P$8") (pintype "output"))
      (node (ref "U2") (pin "P$19") (pinfunction "SYNC_P$19") (pintype "bidirectional"))
      (node (ref "U2") (pin "P$29") (pinfunction "GND_P$29") (pintype "bidirectional"))
      (node (ref "U2") (pin "P$7") (pinfunction "TEST_P$7") (pintype "bidirectional"))
      (node (ref "U3") (pin "P$14") (pinfunction "GND_P$14") (pintype "output"))
      (node (ref "U3") (pin "P$17") (pinfunction "GND_P$17") (pintype "output"))
      (node (ref "U3") (pin "P$18") (pinfunction "GND_P$18") (pintype "output"))
      (node (ref "U3") (pin "P$19") (pinfunction "GND_P$19") (pintype "output"))
      (node (ref "U3") (pin "P$20") (pinfunction "GND_P$20") (pintype "output"))
      (node (ref "U3") (pin "P$21") (pinfunction "GND_P$21") (pintype "output"))
      (node (ref "U3") (pin "P$3") (pinfunction "GND_P$3") (pintype "output"))
      (node (ref "U3") (pin "P$4") (pinfunction "GND_P$4") (pintype "output"))
      (node (ref "U3") (pin "P$7") (pinfunction "GND_P$7") (pintype "output"))
      (node (ref "U3") (pin "P$8") (pinfunction "GND_P$8") (pintype "output"))
      (node (ref "U4") (pin "P$14") (pinfunction "GND_P$14") (pintype "output"))
      (node (ref "U4") (pin "P$17") (pinfunction "GND_P$17") (pintype "output"))
      (node (ref "U4") (pin "P$18") (pinfunction "GND_P$18") (pintype "output"))
      (node (ref "U4") (pin "P$19") (pinfunction "GND_P$19") (pintype "output"))
      (node (ref "U4") (pin "P$20") (pinfunction "GND_P$20") (pintype "output"))
      (node (ref "U4") (pin "P$21") (pinfunction "GND_P$21") (pintype "output"))
      (node (ref "U4") (pin "P$3") (pinfunction "GND_P$3") (pintype "output"))
      (node (ref "U4") (pin "P$4") (pinfunction "GND_P$4") (pintype "output"))
      (node (ref "U4") (pin "P$7") (pinfunction "GND_P$7") (pintype "output"))
      (node (ref "U4") (pin "P$8") (pinfunction "GND_P$8") (pintype "output"))
      (node (ref "U5") (pin "P$14") (pinfunction "GND_P$14") (pintype "output"))
      (node (ref "U5") (pin "P$17") (pinfunction "GND_P$17") (pintype "output"))
      (node (ref "U5") (pin "P$18") (pinfunction "GND_P$18") (pintype "output"))
      (node (ref "U5") (pin "P$19") (pinfunction "GND_P$19") (pintype "output"))
      (node (ref "U5") (pin "P$20") (pinfunction "GND_P$20") (pintype "output"))
      (node (ref "U5") (pin "P$21") (pinfunction "GND_P$21") (pintype "output"))
      (node (ref "U5") (pin "P$3") (pinfunction "GND_P$3") (pintype "output"))
      (node (ref "U5") (pin "P$4") (pinfunction "GND_P$4") (pintype "output"))
      (node (ref "U5") (pin "P$7") (pinfunction "GND_P$7") (pintype "output"))
      (node (ref "U5") (pin "P$8") (pinfunction "GND_P$8") (pintype "output"))
      (node (ref "U6") (pin "P$14") (pinfunction "GND_P$14") (pintype "output"))
      (node (ref "U6") (pin "P$17") (pinfunction "GND_P$17") (pintype "output"))
      (node (ref "U6") (pin "P$18") (pinfunction "GND_P$18") (pintype "output"))
      (node (ref "U6") (pin "P$19") (pinfunction "GND_P$19") (pintype "output"))
      (node (ref "U6") (pin "P$20") (pinfunction "GND_P$20") (pintype "output"))
      (node (ref "U6") (pin "P$21") (pinfunction "GND_P$21") (pintype "output"))
      (node (ref "U6") (pin "P$3") (pinfunction "GND_P$3") (pintype "output"))
      (node (ref "U6") (pin "P$4") (pinfunction "GND_P$4") (pintype "output"))
      (node (ref "U6") (pin "P$7") (pinfunction "GND_P$7") (pintype "output"))
      (node (ref "U6") (pin "P$8") (pinfunction "GND_P$8") (pintype "output"))
      (node (ref "U7") (pin "P$14") (pinfunction "GND_P$14") (pintype "output"))
      (node (ref "U7") (pin "P$17") (pinfunction "GND_P$17") (pintype "output"))
      (node (ref "U7") (pin "P$18") (pinfunction "GND_P$18") (pintype "output"))
      (node (ref "U7") (pin "P$19") (pinfunction "GND_P$19") (pintype "output"))
      (node (ref "U7") (pin "P$20") (pinfunction "GND_P$20") (pintype "output"))
      (node (ref "U7") (pin "P$21") (pinfunction "GND_P$21") (pintype "output"))
      (node (ref "U7") (pin "P$3") (pinfunction "GND_P$3") (pintype "output"))
      (node (ref "U7") (pin "P$4") (pinfunction "GND_P$4") (pintype "output"))
      (node (ref "U7") (pin "P$7") (pinfunction "GND_P$7") (pintype "output"))
      (node (ref "U7") (pin "P$8") (pinfunction "GND_P$8") (pintype "output"))
      (node (ref "U8") (pin "P$14") (pinfunction "GND_P$14") (pintype "output"))
      (node (ref "U8") (pin "P$17") (pinfunction "GND_P$17") (pintype "output"))
      (node (ref "U8") (pin "P$18") (pinfunction "GND_P$18") (pintype "output"))
      (node (ref "U8") (pin "P$19") (pinfunction "GND_P$19") (pintype "output"))
      (node (ref "U8") (pin "P$20") (pinfunction "GND_P$20") (pintype "output"))
      (node (ref "U8") (pin "P$21") (pinfunction "GND_P$21") (pintype "output"))
      (node (ref "U8") (pin "P$3") (pinfunction "GND_P$3") (pintype "output"))
      (node (ref "U8") (pin "P$4") (pinfunction "GND_P$4") (pintype "output"))
      (node (ref "U8") (pin "P$7") (pinfunction "GND_P$7") (pintype "output"))
      (node (ref "U8") (pin "P$8") (pinfunction "GND_P$8") (pintype "output"))
      (node (ref "U9") (pin "P$14") (pinfunction "GND_P$14") (pintype "output"))
      (node (ref "U9") (pin "P$17") (pinfunction "GND_P$17") (pintype "output"))
      (node (ref "U9") (pin "P$18") (pinfunction "GND_P$18") (pintype "output"))
      (node (ref "U9") (pin "P$19") (pinfunction "GND_P$19") (pintype "output"))
      (node (ref "U9") (pin "P$20") (pinfunction "GND_P$20") (pintype "output"))
      (node (ref "U9") (pin "P$21") (pinfunction "GND_P$21") (pintype "output"))
      (node (ref "U9") (pin "P$3") (pinfunction "GND_P$3") (pintype "output"))
      (node (ref "U9") (pin "P$4") (pinfunction "GND_P$4") (pintype "output"))
      (node (ref "U9") (pin "P$7") (pinfunction "GND_P$7") (pintype "output"))
      (node (ref "U9") (pin "P$8") (pinfunction "GND_P$8") (pintype "output"))
    )
    (net (code "31") (name "I2C_SCL") (class "Default")
      (node (ref "H1") (pin "1.43") (pinfunction "1.43_1.43") (pintype "bidirectional"))
      (node (ref "R31") (pin "1") (pinfunction "1_1") (pintype "passive"))
      (node (ref "U1") (pin "P$9") (pinfunction "P$9_P$9") (pintype "bidirectional"))
    )
    (net (code "32") (name "I2C_SDA") (class "Default")
      (node (ref "H1") (pin "1.41") (pinfunction "1.41_1.41") (pintype "bidirectional"))
      (node (ref "R30") (pin "1") (pinfunction "1_1") (pintype "passive"))
      (node (ref "U1") (pin "P$8") (pinfunction "P$8_P$8") (pintype "bidirectional"))
    )
    (net (code "33") (name "Net-(+3V3_SW1-Pad1)") (class "Default")
      (node (ref "+3V3_SW1") (pin "1") (pinfunction "1_1") (pintype "bidirectional"))
      (node (ref "R48") (pin "2") (pinfunction "2_2") (pintype "passive"))
    )
    (net (code "34") (name "Net-(+3V3_SW2-Pad1)") (class "Default")
      (node (ref "+3V3_SW2") (pin "1") (pinfunction "1_1") (pintype "bidirectional"))
      (node (ref "R55") (pin "2") (pinfunction "2_2") (pintype "passive"))
    )
    (net (code "35") (name "Net-(+3V3_SW3-Pad1)") (class "Default")
      (node (ref "+3V3_SW3") (pin "1") (pinfunction "1_1") (pintype "bidirectional"))
      (node (ref "R60") (pin "2") (pinfunction "2_2") (pintype "passive"))
    )
    (net (code "36") (name "Net-(+3V_BUS-Pad1)") (class "Default")
      (node (ref "+3V_BUS") (pin "1") (pinfunction "1_1") (pintype "bidirectional"))
      (node (ref "R49") (pin "2") (pinfunction "2_2") (pintype "passive"))
    )
    (net (code "37") (name "Net-(+5V_BUS-Pad1)") (class "Default")
      (node (ref "+5V_BUS") (pin "1") (pinfunction "1_1") (pintype "bidirectional"))
      (node (ref "R50") (pin "2") (pinfunction "2_2") (pintype "passive"))
    )
    (net (code "38") (name "Net-(+5V_SW1-Pad1)") (class "Default")
      (node (ref "+5V_SW1") (pin "1") (pinfunction "1_1") (pintype "bidirectional"))
      (node (ref "R51") (pin "2") (pinfunction "2_2") (pintype "passive"))
    )
    (net (code "39") (name "Net-(+5V_SW2-Pad1)") (class "Default")
      (node (ref "+5V_SW2") (pin "1") (pinfunction "1_1") (pintype "bidirectional"))
      (node (ref "R41") (pin "2") (pinfunction "2_2") (pintype "passive"))
    )
    (net (code "40") (name "Net-(+12V_SW1-Pad1)") (class "Default")
      (node (ref "+12V_SW1") (pin "1") (pinfunction "1_1") (pintype "bidirectional"))
      (node (ref "R52") (pin "2") (pinfunction "2_2") (pintype "passive"))
    )
    (net (code "41") (name "Net-(C11-Pad1)") (class "Default")
      (node (ref "C11") (pin "1") (pinfunction "1_1") (pintype "passive"))
      (node (ref "R3") (pin "1") (pinfunction "1_1") (pintype "passive"))
    )
    (net (code "42") (name "Net-(D1-PadC)") (class "Default")
      (node (ref "D1") (pin "C") (pinfunction "C_C") (pintype "passive"))
      (node (ref "J2") (pin "1") (pinfunction "1_1") (pintype "bidirectional"))
      (node (ref "J3") (pin "1") (pinfunction "1_1") (pintype "bidirectional"))
      (node (ref "R34") (pin "2") (pinfunction "2_2") (pintype "passive"))
    )
    (net (code "43") (name "Net-(D2-PadA)") (class "Default")
      (node (ref "D2") (pin "A") (pinfunction "A_A") (pintype "passive"))
      (node (ref "J6") (pin "VBUS") (pinfunction "VBUS_VBUS") (pintype "power_in"))
    )
    (net (code "44") (name "Net-(D3-PadC)") (class "Default")
      (node (ref "D3") (pin "C") (pinfunction "C_C") (pintype "passive"))
      (node (ref "J4") (pin "1") (pinfunction "1_1") (pintype "bidirectional"))
      (node (ref "J5") (pin "1") (pinfunction "1_1") (pintype "bidirectional"))
      (node (ref "R36") (pin "1") (pinfunction "1_1") (pintype "passive"))
    )
    (net (code "45") (name "Net-(H1-PadP$4)") (class "Default")
      (node (ref "H1") (pin "P$4") (pinfunction "P$4_P$4") (pintype "bidirectional"))
      (node (ref "R66") (pin "1") (pinfunction "1_1") (pintype "passive"))
    )
    (net (code "46") (name "Net-(J3-Pad2)") (class "Default")
      (node (ref "J3") (pin "2") (pinfunction "2_2") (pintype "bidirectional"))
      (node (ref "R33") (pin "1") (pinfunction "1_1") (pintype "passive"))
      (node (ref "R35") (pin "2") (pinfunction "2_2") (pintype "passive"))
    )
    (net (code "47") (name "Net-(J4-Pad2)") (class "Default")
      (node (ref "J4") (pin "2") (pinfunction "2_2") (pintype "bidirectional"))
      (node (ref "R61") (pin "1") (pinfunction "1_1") (pintype "passive"))
      (node (ref "R62") (pin "1") (pinfunction "1_1") (pintype "passive"))
    )
    (net (code "48") (name "Net-(J12-Pad1)") (class "Default")
      (node (ref "J12") (pin "1") (pinfunction "1_1") (pintype "bidirectional"))
      (node (ref "L10") (pin "P$1") (pinfunction "P$1_P$1") (pintype "bidirectional"))
    )
    (net (code "49") (name "Net-(L2-+)") (class "Default")
      (node (ref "L2") (pin "P$1") (pinfunction "+_P$1") (pintype "bidirectional"))
      (node (ref "U3") (pin "P$5") (pinfunction "SW_P$5") (pintype "output"))
      (node (ref "U3") (pin "P$6") (pinfunction "SW_P$6") (pintype "output"))
    )
    (net (code "50") (name "Net-(L3-+)") (class "Default")
      (node (ref "L3") (pin "P$1") (pinfunction "+_P$1") (pintype "bidirectional"))
      (node (ref "U4") (pin "P$5") (pinfunction "SW_P$5") (pintype "output"))
      (node (ref "U4") (pin "P$6") (pinfunction "SW_P$6") (pintype "output"))
    )
    (net (code "51") (name "Net-(L4-+)") (class "Default")
      (node (ref "L4") (pin "P$1") (pinfunction "+_P$1") (pintype "bidirectional"))
      (node (ref "U5") (pin "P$5") (pinfunction "SW_P$5") (pintype "output"))
      (node (ref "U5") (pin "P$6") (pinfunction "SW_P$6") (pintype "output"))
    )
    (net (code "52") (name "Net-(L5-+)") (class "Default")
      (node (ref "L5") (pin "P$1") (pinfunction "+_P$1") (pintype "bidirectional"))
      (node (ref "U6") (pin "P$5") (pinfunction "SW_P$5") (pintype "output"))
      (node (ref "U6") (pin "P$6") (pinfunction "SW_P$6") (pintype "output"))
    )
    (net (code "53") (name "Net-(L6-+)") (class "Default")
      (node (ref "L6") (pin "P$1") (pinfunction "+_P$1") (pintype "bidirectional"))
      (node (ref "U7") (pin "P$5") (pinfunction "SW_P$5") (pintype "output"))
      (node (ref "U7") (pin "P$6") (pinfunction "SW_P$6") (pintype "output"))
    )
    (net (code "54") (name "Net-(L7-+)") (class "Default")
      (node (ref "L7") (pin "P$1") (pinfunction "+_P$1") (pintype "bidirectional"))
      (node (ref "U8") (pin "P$5") (pinfunction "SW_P$5") (pintype "output"))
      (node (ref "U8") (pin "P$6") (pinfunction "SW_P$6") (pintype "output"))
    )
    (net (code "55") (name "Net-(L8-+)") (class "Default")
      (node (ref "L8") (pin "P$1") (pinfunction "+_P$1") (pintype "bidirectional"))
      (node (ref "U9") (pin "P$5") (pinfunction "SW_P$5") (pintype "output"))
      (node (ref "U9") (pin "P$6") (pinfunction "SW_P$6") (pintype "output"))
    )
    (net (code "56") (name "Net-(L9-+)") (class "Default")
      (node (ref "L9") (pin "P$1") (pinfunction "+_P$1") (pintype "bidirectional"))
      (node (ref "U10") (pin "P$5") (pinfunction "SW_P$5") (pintype "output"))
      (node (ref "U10") (pin "P$6") (pinfunction "SW_P$6") (pintype "output"))
    )
    (net (code "57") (name "Net-(M1-G)") (class "Default")
      (node (ref "M1") (pin "P$1") (pinfunction "G_P$1") (pintype "input"))
      (node (ref "U2") (pin "P$1") (pinfunction "TG1_P$1") (pintype "bidirectional"))
    )
    (net (code "58") (name "Net-(M2-G)") (class "Default")
      (node (ref "M2") (pin "P$1") (pinfunction "G_P$1") (pintype "input"))
      (node (ref "U2") (pin "P$26") (pinfunction "BG1_P$26") (pintype "bidirectional"))
    )
    (net (code "59") (name "Net-(M3-G)") (class "Default")
      (node (ref "M3") (pin "P$1") (pinfunction "G_P$1") (pintype "input"))
      (node (ref "U2") (pin "P$25") (pinfunction "BG2_P$25") (pintype "bidirectional"))
    )
    (net (code "60") (name "Net-(M4-G)") (class "Default")
      (node (ref "M4") (pin "P$1") (pinfunction "G_P$1") (pintype "input"))
      (node (ref "U2") (pin "P$22") (pinfunction "TG2_P$22") (pintype "bidirectional"))
    )
    (net (code "61") (name "Net-(R32-Pad2)") (class "Default")
      (node (ref "R32") (pin "2") (pinfunction "2_2") (pintype "passive"))
      (node (ref "R8") (pin "1") (pinfunction "1_1") (pintype "passive"))
    )
    (net (code "62") (name "Net-(U2-BST1)") (class "Default")
      (node (ref "C3") (pin "2") (pinfunction "2_2") (pintype "passive"))
      (node (ref "U2") (pin "P$27") (pinfunction "BST1_P$27") (pintype "bidirectional"))
    )
    (net (code "63") (name "Net-(U2-BST2)") (class "Default")
      (node (ref "C10") (pin "2") (pinfunction "2_2") (pintype "passive"))
      (node (ref "U2") (pin "P$24") (pinfunction "BST2_P$24") (pintype "bidirectional"))
    )
    (net (code "64") (name "Net-(U2-CTRL)") (class "Default")
      (node (ref "C5") (pin "1") (pinfunction "1_1") (pintype "passive"))
      (node (ref "U2") (pin "P$10") (pinfunction "CTRL_P$10") (pintype "bidirectional"))
      (node (ref "U2") (pin "P$8") (pinfunction "LOADEN_P$8") (pintype "bidirectional"))
      (node (ref "U2") (pin "P$9") (pinfunction "VREF_P$9") (pintype "bidirectional"))
    )
    (net (code "65") (name "Net-(U2-EN)") (class "Default")
      (node (ref "R1") (pin "1") (pinfunction "1_1") (pintype "passive"))
      (node (ref "R2") (pin "2") (pinfunction "2_2") (pintype "passive"))
      (node (ref "U2") (pin "P$6") (pinfunction "EN_P$6") (pintype "bidirectional"))
    )
    (net (code "66") (name "Net-(U2-FB)") (class "Default")
      (node (ref "R32") (pin "1") (pinfunction "1_1") (pintype "passive"))
      (node (ref "R9") (pin "2") (pinfunction "2_2") (pintype "passive"))
      (node (ref "U2") (pin "P$16") (pinfunction "FB_P$16") (pintype "bidirectional"))
    )
    (net (code "67") (name "Net-(U2-INTVCC)") (class "Default")
      (node (ref "C8") (pin "1") (pinfunction "1_1") (pintype "passive"))
      (node (ref "R5") (pin "2") (pinfunction "2_2") (pintype "passive"))
      (node (ref "U2") (pin "P$5") (pinfunction "INTVCC_P$5") (pintype "bidirectional"))
    )
    (net (code "68") (name "Net-(U2-ISP)") (class "Default")
      (node (ref "C12") (pin "1") (pinfunction "1_1") (pintype "passive"))
      (node (ref "C17") (pin "1") (pinfunction "1_1") (pintype "passive"))
      (node (ref "C74") (pin "1") (pinfunction "1_1") (pintype "passive"))
      (node (ref "C75") (pin "1") (pinfunction "1_1") (pintype "passive"))
      (node (ref "C76") (pin "1") (pinfunction "1_1") (pintype "passive"))
      (node (ref "C77") (pin "1") (pinfunction "1_1") (pintype "passive"))
      (node (ref "C9") (pin "1") (pinfunction "1_1") (pintype "passive"))
      (node (ref "M4") (pin "P$5") (pinfunction "D_P$5") (pintype "output"))
      (node (ref "M4") (pin "P$6") (pinfunction "D_P$6") (pintype "output"))
      (node (ref "M4") (pin "P$7") (pinfunction "D_P$7") (pintype "output"))
      (node (ref "M4") (pin "P$8") (pinfunction "D_P$8") (pintype "output"))
      (node (ref "M4") (pin "P$9") (pinfunction "D_P$9") (pintype "output"))
      (node (ref "R7") (pin "1") (pinfunction "1_1") (pintype "passive"))
      (node (ref "U2") (pin "P$11") (pinfunction "ISP_P$11") (pintype "bidirectional"))
      (node (ref "U2") (pin "P$21") (pinfunction "VOUT_P$21") (pintype "bidirectional"))
    )
    (net (code "69") (name "Net-(U2-LSN)") (class "Default")
      (node (ref "L1") (pin "P$1") (pinfunction "P$1_P$1") (pintype "bidirectional"))
      (node (ref "R6") (pin "1") (pinfunction "1_1") (pintype "passive"))
      (node (ref "U2") (pin "P$3") (pinfunction "LSN_P$3") (pintype "bidirectional"))
    )
    (net (code "70") (name "Net-(U2-LSP)") (class "Default")
      (node (ref "C3") (pin "1") (pinfunction "1_1") (pintype "passive"))
      (node (ref "M1") (pin "P$2") (pinfunction "S_P$2") (pintype "input"))
      (node (ref "M1") (pin "P$3") (pinfunction "S_P$3") (pintype "input"))
      (node (ref "M1") (pin "P$4") (pinfunction "S_P$4") (pintype "input"))
      (node (ref "M2") (pin "P$5") (pinfunction "D_P$5") (pintype "output"))
      (node (ref "M2") (pin "P$6") (pinfunction "D_P$6") (pintype "output"))
      (node (ref "M2") (pin "P$7") (pinfunction "D_P$7") (pintype "output"))
      (node (ref "M2") (pin "P$8") (pinfunction "D_P$8") (pintype "output"))
      (node (ref "M2") (pin "P$9") (pinfunction "D_P$9") (pintype "output"))
      (node (ref "R6") (pin "2") (pinfunction "2_2") (pintype "passive"))
      (node (ref "U2") (pin "P$2") (pinfunction "LSP_P$2") (pintype "bidirectional"))
      (node (ref "U2") (pin "P$28") (pinfunction "SW1_P$28") (pintype "bidirectional"))
    )
    (net (code "71") (name "Net-(U2-NPGOOD)") (class "Default")
      (node (ref "R5") (pin "1") (pinfunction "1_1") (pintype "passive"))
      (node (ref "U2") (pin "P$14") (pinfunction "NPGOOD_P$14") (pintype "bidirectional"))
    )
    (net (code "72") (name "Net-(U2-RT)") (class "Default")
      (node (ref "R4") (pin "2") (pinfunction "2_2") (pintype "passive"))
      (node (ref "U2") (pin "P$18") (pinfunction "RT_P$18") (pintype "bidirectional"))
    )
    (net (code "73") (name "Net-(U2-SS)") (class "Default")
      (node (ref "C6") (pin "1") (pinfunction "1_1") (pintype "passive"))
      (node (ref "U2") (pin "P$15") (pinfunction "SS_P$15") (pintype "bidirectional"))
    )
    (net (code "74") (name "Net-(U2-SW2)") (class "Default")
      (node (ref "C10") (pin "1") (pinfunction "1_1") (pintype "passive"))
      (node (ref "L1") (pin "P$2") (pinfunction "P$2_P$2") (pintype "bidirectional"))
      (node (ref "M3") (pin "P$5") (pinfunction "D_P$5") (pintype "output"))
      (node (ref "M3") (pin "P$6") (pinfunction "D_P$6") (pintype "output"))
      (node (ref "M3") (pin "P$7") (pinfunction "D_P$7") (pintype "output"))
      (node (ref "M3") (pin "P$8") (pinfunction "D_P$8") (pintype "output"))
      (node (ref "M3") (pin "P$9") (pinfunction "D_P$9") (pintype "output"))
      (node (ref "M4") (pin "P$2") (pinfunction "S_P$2") (pintype "input"))
      (node (ref "M4") (pin "P$3") (pinfunction "S_P$3") (pintype "input"))
      (node (ref "M4") (pin "P$4") (pinfunction "S_P$4") (pintype "input"))
      (node (ref "U2") (pin "P$23") (pinfunction "SW2_P$23") (pintype "bidirectional"))
    )
    (net (code "75") (name "Net-(U2-VC)") (class "Default")
      (node (ref "C7") (pin "1") (pinfunction "1_1") (pintype "passive"))
      (node (ref "R3") (pin "2") (pinfunction "2_2") (pintype "passive"))
      (node (ref "U2") (pin "P$17") (pinfunction "VC_P$17") (pintype "bidirectional"))
    )
    (net (code "76") (name "Net-(U2-VIN)") (class "Default")
      (node (ref "C1") (pin "1") (pinfunction "1_1") (pintype "passive"))
      (node (ref "C15") (pin "1") (pinfunction "1_1") (pintype "passive"))
      (node (ref "C16") (pin "1") (pinfunction "1_1") (pintype "passive"))
      (node (ref "C2") (pin "1") (pinfunction "1_1") (pintype "passive"))
      (node (ref "C4") (pin "1") (pinfunction "1_1") (pintype "passive"))
      (node (ref "L10") (pin "P$2") (pinfunction "P$2_P$2") (pintype "bidirectional"))
      (node (ref "M1") (pin "P$5") (pinfunction "D_P$5") (pintype "output"))
      (node (ref "M1") (pin "P$6") (pinfunction "D_P$6") (pintype "output"))
      (node (ref "M1") (pin "P$7") (pinfunction "D_P$7") (pintype "output"))
      (node (ref "M1") (pin "P$8") (pinfunction "D_P$8") (pintype "output"))
      (node (ref "M1") (pin "P$9") (pinfunction "D_P$9") (pintype "output"))
      (node (ref "R1") (pin "2") (pinfunction "2_2") (pintype "passive"))
      (node (ref "U2") (pin "P$4") (pinfunction "VIN_P$4") (pintype "bidirectional"))
    )
    (net (code "77") (name "Net-(U3-FB)") (class "Default")
      (node (ref "C21") (pin "1") (pinfunction "1_1") (pintype "passive"))
      (node (ref "R11") (pin "2") (pinfunction "2_2") (pintype "passive"))
      (node (ref "R12") (pin "2") (pinfunction "2_2") (pintype "passive"))
      (node (ref "U3") (pin "P$13") (pinfunction "FB_P$13") (pintype "output"))
    )
    (net (code "78") (name "Net-(U3-INTVCC)") (class "Default")
      (node (ref "C19") (pin "1") (pinfunction "1_1") (pintype "passive"))
      (node (ref "U3") (pin "P$2") (pinfunction "INTVCC_P$2") (pintype "output"))
    )
    (net (code "79") (name "Net-(U3-RT)") (class "Default")
      (node (ref "R10") (pin "2") (pinfunction "2_2") (pintype "passive"))
      (node (ref "U3") (pin "P$1") (pinfunction "RT_P$1") (pintype "output"))
    )
    (net (code "80") (name "Net-(U3-TRSS)") (class "Default")
      (node (ref "C18") (pin "1") (pinfunction "1_1") (pintype "passive"))
      (node (ref "U3") (pin "P$15") (pinfunction "TRSS_P$15") (pintype "output"))
    )
    (net (code "81") (name "Net-(U4-FB)") (class "Default")
      (node (ref "C26") (pin "1") (pinfunction "1_1") (pintype "passive"))
      (node (ref "R15") (pin "2") (pinfunction "2_2") (pintype "passive"))
      (node (ref "R16") (pin "2") (pinfunction "2_2") (pintype "passive"))
      (node (ref "U4") (pin "P$13") (pinfunction "FB_P$13") (pintype "output"))
    )
    (net (code "82") (name "Net-(U4-INTVCC)") (class "Default")
      (node (ref "C24") (pin "1") (pinfunction "1_1") (pintype "passive"))
      (node (ref "U4") (pin "P$2") (pinfunction "INTVCC_P$2") (pintype "output"))
    )
    (net (code "83") (name "Net-(U4-RT)") (class "Default")
      (node (ref "R14") (pin "2") (pinfunction "2_2") (pintype "passive"))
      (node (ref "U4") (pin "P$1") (pinfunction "RT_P$1") (pintype "output"))
    )
    (net (code "84") (name "Net-(U4-TRSS)") (class "Default")
      (node (ref "C23") (pin "1") (pinfunction "1_1") (pintype "passive"))
      (node (ref "U4") (pin "P$15") (pinfunction "TRSS_P$15") (pintype "output"))
    )
    (net (code "85") (name "Net-(U5-FB)") (class "Default")
      (node (ref "C31") (pin "1") (pinfunction "1_1") (pintype "passive"))
      (node (ref "R19") (pin "2") (pinfunction "2_2") (pintype "passive"))
      (node (ref "R20") (pin "2") (pinfunction "2_2") (pintype "passive"))
      (node (ref "U5") (pin "P$13") (pinfunction "FB_P$13") (pintype "output"))
    )
    (net (code "86") (name "Net-(U5-INTVCC)") (class "Default")
      (node (ref "C29") (pin "1") (pinfunction "1_1") (pintype "passive"))
      (node (ref "U5") (pin "P$2") (pinfunction "INTVCC_P$2") (pintype "output"))
    )
    (net (code "87") (name "Net-(U5-RT)") (class "Default")
      (node (ref "R18") (pin "2") (pinfunction "2_2") (pintype "passive"))
      (node (ref "U5") (pin "P$1") (pinfunction "RT_P$1") (pintype "output"))
    )
    (net (code "88") (name "Net-(U5-TRSS)") (class "Default")
      (node (ref "C28") (pin "1") (pinfunction "1_1") (pintype "passive"))
      (node (ref "U5") (pin "P$15") (pinfunction "TRSS_P$15") (pintype "output"))
    )
    (net (code "89") (name "Net-(U6-FB)") (class "Default")
      (node (ref "C36") (pin "1") (pinfunction "1_1") (pintype "passive"))
      (node (ref "R23") (pin "2") (pinfunction "2_2") (pintype "passive"))
      (node (ref "R24") (pin "2") (pinfunction "2_2") (pintype "passive"))
      (node (ref "U6") (pin "P$13") (pinfunction "FB_P$13") (pintype "output"))
    )
    (net (code "90") (name "Net-(U6-INTVCC)") (class "Default")
      (node (ref "C34") (pin "1") (pinfunction "1_1") (pintype "passive"))
      (node (ref "U6") (pin "P$2") (pinfunction "INTVCC_P$2") (pintype "output"))
    )
    (net (code "91") (name "Net-(U6-RT)") (class "Default")
      (node (ref "R22") (pin "2") (pinfunction "2_2") (pintype "passive"))
      (node (ref "U6") (pin "P$1") (pinfunction "RT_P$1") (pintype "output"))
    )
    (net (code "92") (name "Net-(U6-TRSS)") (class "Default")
      (node (ref "C33") (pin "1") (pinfunction "1_1") (pintype "passive"))
      (node (ref "U6") (pin "P$15") (pinfunction "TRSS_P$15") (pintype "output"))
    )
    (net (code "93") (name "Net-(U7-FB)") (class "Default")
      (node (ref "C41") (pin "1") (pinfunction "1_1") (pintype "passive"))
      (node (ref "R27") (pin "2") (pinfunction "2_2") (pintype "passive"))
      (node (ref "R28") (pin "2") (pinfunction "2_2") (pintype "passive"))
      (node (ref "U7") (pin "P$13") (pinfunction "FB_P$13") (pintype "output"))
    )
    (net (code "94") (name "Net-(U7-INTVCC)") (class "Default")
      (node (ref "C39") (pin "1") (pinfunction "1_1") (pintype "passive"))
      (node (ref "U7") (pin "P$2") (pinfunction "INTVCC_P$2") (pintype "output"))
    )
    (net (code "95") (name "Net-(U7-RT)") (class "Default")
      (node (ref "R26") (pin "2") (pinfunction "2_2") (pintype "passive"))
      (node (ref "U7") (pin "P$1") (pinfunction "RT_P$1") (pintype "output"))
    )
    (net (code "96") (name "Net-(U7-TRSS)") (class "Default")
      (node (ref "C38") (pin "1") (pinfunction "1_1") (pintype "passive"))
      (node (ref "U7") (pin "P$15") (pinfunction "TRSS_P$15") (pintype "output"))
    )
    (net (code "97") (name "Net-(U8-FB)") (class "Default")
      (node (ref "C51") (pin "1") (pinfunction "1_1") (pintype "passive"))
      (node (ref "R38") (pin "2") (pinfunction "2_2") (pintype "passive"))
      (node (ref "R39") (pin "2") (pinfunction "2_2") (pintype "passive"))
      (node (ref "U8") (pin "P$13") (pinfunction "FB_P$13") (pintype "output"))
    )
    (net (code "98") (name "Net-(U8-INTVCC)") (class "Default")
      (node (ref "C49") (pin "1") (pinfunction "1_1") (pintype "passive"))
      (node (ref "U8") (pin "P$2") (pinfunction "INTVCC_P$2") (pintype "output"))
    )
    (net (code "99") (name "Net-(U8-PG)") (class "Default")
      (node (ref "R40") (pin "2") (pinfunction "2_2") (pintype "passive"))
      (node (ref "U8") (pin "P$12") (pinfunction "PG_P$12") (pintype "input"))
    )
    (net (code "100") (name "Net-(U8-RT)") (class "Default")
      (node (ref "R37") (pin "2") (pinfunction "2_2") (pintype "passive"))
      (node (ref "U8") (pin "P$1") (pinfunction "RT_P$1") (pintype "output"))
    )
    (net (code "101") (name "Net-(U8-TRSS)") (class "Default")
      (node (ref "C48") (pin "1") (pinfunction "1_1") (pintype "passive"))
      (node (ref "U8") (pin "P$15") (pinfunction "TRSS_P$15") (pintype "output"))
    )
    (net (code "102") (name "Net-(U9-FB)") (class "Default")
      (node (ref "C56") (pin "1") (pinfunction "1_1") (pintype "passive"))
      (node (ref "R43") (pin "2") (pinfunction "2_2") (pintype "passive"))
      (node (ref "R53") (pin "2") (pinfunction "2_2") (pintype "passive"))
      (node (ref "U9") (pin "P$13") (pinfunction "FB_P$13") (pintype "output"))
    )
    (net (code "103") (name "Net-(U9-INTVCC)") (class "Default")
      (node (ref "C54") (pin "1") (pinfunction "1_1") (pintype "passive"))
      (node (ref "U9") (pin "P$2") (pinfunction "INTVCC_P$2") (pintype "output"))
    )
    (net (code "104") (name "Net-(U9-PG)") (class "Default")
      (node (ref "R54") (pin "2") (pinfunction "2_2") (pintype "passive"))
      (node (ref "U9") (pin "P$12") (pinfunction "PG_P$12") (pintype "input"))
    )
    (net (code "105") (name "Net-(U9-RT)") (class "Default")
      (node (ref "R42") (pin "2") (pinfunction "2_2") (pintype "passive"))
      (node (ref "U9") (pin "P$1") (pinfunction "RT_P$1") (pintype "output"))
    )
    (net (code "106") (name "Net-(U9-TRSS)") (class "Default")
      (node (ref "C53") (pin "1") (pinfunction "1_1") (pintype "passive"))
      (node (ref "U9") (pin "P$15") (pinfunction "TRSS_P$15") (pintype "output"))
    )
    (net (code "107") (name "Net-(U10-FB)") (class "Default")
      (node (ref "C61") (pin "1") (pinfunction "1_1") (pintype "passive"))
      (node (ref "R57") (pin "2") (pinfunction "2_2") (pintype "passive"))
      (node (ref "R58") (pin "2") (pinfunction "2_2") (pintype "passive"))
      (node (ref "U10") (pin "P$13") (pinfunction "FB_P$13") (pintype "output"))
    )
    (net (code "108") (name "Net-(U10-INTVCC)") (class "Default")
      (node (ref "C59") (pin "1") (pinfunction "1_1") (pintype "passive"))
      (node (ref "U10") (pin "P$2") (pinfunction "INTVCC_P$2") (pintype "output"))
    )
    (net (code "109") (name "Net-(U10-PG)") (class "Default")
      (node (ref "R59") (pin "2") (pinfunction "2_2") (pintype "passive"))
      (node (ref "U10") (pin "P$12") (pinfunction "PG_P$12") (pintype "input"))
    )
    (net (code "110") (name "Net-(U10-RT)") (class "Default")
      (node (ref "R56") (pin "2") (pinfunction "2_2") (pintype "passive"))
      (node (ref "U10") (pin "P$1") (pinfunction "RT_P$1") (pintype "output"))
    )
    (net (code "111") (name "Net-(U10-TRSS)") (class "Default")
      (node (ref "C58") (pin "1") (pinfunction "1_1") (pintype "passive"))
      (node (ref "U10") (pin "P$15") (pinfunction "TRSS_P$15") (pintype "output"))
    )
    (net (code "112") (name "SOLAR") (class "Default")
      (node (ref "D2") (pin "C") (pinfunction "C_C") (pintype "passive"))
      (node (ref "J12") (pin "2") (pinfunction "2_2") (pintype "bidirectional"))
      (node (ref "R34") (pin "1") (pinfunction "1_1") (pintype "passive"))
      (node (ref "R35") (pin "1") (pinfunction "1_1") (pintype "passive"))
      (node (ref "R36") (pin "2") (pinfunction "2_2") (pintype "passive"))
      (node (ref "R62") (pin "2") (pinfunction "2_2") (pintype "passive"))
    )
    (net (code "113") (name "SW1_PGOOD") (class "Default")
      (node (ref "R29") (pin "2") (pinfunction "2_2") (pintype "passive"))
      (node (ref "U1") (pin "P$29") (pinfunction "P$29_P$29") (pintype "bidirectional"))
      (node (ref "U7") (pin "P$12") (pinfunction "PG_P$12") (pintype "input"))
    )
    (net (code "114") (name "SW2_PGOOD") (class "Default")
      (node (ref "R21") (pin "2") (pinfunction "2_2") (pintype "passive"))
      (node (ref "U1") (pin "P$28") (pinfunction "P$28_P$28") (pintype "bidirectional"))
      (node (ref "U5") (pin "P$12") (pinfunction "PG_P$12") (pintype "input"))
    )
    (net (code "115") (name "SW3_PGOOD") (class "Default")
      (node (ref "R13") (pin "2") (pinfunction "2_2") (pintype "passive"))
      (node (ref "U3") (pin "P$12") (pinfunction "PG_P$12") (pintype "input"))
    )
    (net (code "116") (name "SW3_V_SENSE") (class "Default")
      (node (ref "R44") (pin "1") (pinfunction "1_1") (pintype "passive"))
      (node (ref "R45") (pin "1") (pinfunction "1_1") (pintype "passive"))
      (node (ref "U1") (pin "P$4") (pinfunction "P$4_P$4") (pintype "bidirectional"))
    )
    (net (code "117") (name "V_BATT") (class "Default")
      (node (ref "C20") (pin "1") (pinfunction "1_1") (pintype "passive"))
      (node (ref "C30") (pin "1") (pinfunction "1_1") (pintype "passive"))
      (node (ref "C40") (pin "1") (pinfunction "1_1") (pintype "passive"))
      (node (ref "C50") (pin "1") (pinfunction "1_1") (pintype "passive"))
      (node (ref "C55") (pin "1") (pinfunction "1_1") (pintype "passive"))
      (node (ref "C60") (pin "1") (pinfunction "1_1") (pintype "passive"))
      (node (ref "C78") (pin "1") (pinfunction "1_1") (pintype "passive"))
      (node (ref "C79") (pin "1") (pinfunction "1_1") (pintype "passive"))
      (node (ref "C80") (pin "1") (pinfunction "1_1") (pintype "passive"))
      (node (ref "C81") (pin "1") (pinfunction "1_1") (pintype "passive"))
      (node (ref "D4") (pin "A") (pinfunction "A_A") (pintype "passive"))
      (node (ref "D4") (pin "C") (pinfunction "C_C") (pintype "passive"))
      (node (ref "H1") (pin "2.33") (pinfunction "2.33_2.33") (pintype "bidirectional"))
      (node (ref "H1") (pin "2.34") (pinfunction "2.34_2.34") (pintype "bidirectional"))
      (node (ref "H1") (pin "2.45") (pinfunction "2.45_2.45") (pintype "bidirectional"))
      (node (ref "H1") (pin "2.46") (pinfunction "2.46_2.46") (pintype "bidirectional"))
      (node (ref "J14") (pin "2") (pinfunction "2_2") (pintype "bidirectional"))
      (node (ref "J16") (pin "2") (pinfunction "2_2") (pintype "bidirectional"))
      (node (ref "R46") (pin "1") (pinfunction "1_1") (pintype "passive"))
      (node (ref "R7") (pin "2") (pinfunction "2_2") (pintype "passive"))
      (node (ref "R8") (pin "2") (pinfunction "2_2") (pintype "passive"))
      (node (ref "U10") (pin "P$10") (pinfunction "VIN_P$10") (pintype "input"))
      (node (ref "U10") (pin "P$9") (pinfunction "VIN_P$9") (pintype "input"))
      (node (ref "U2") (pin "P$12") (pinfunction "ISN_P$12") (pintype "bidirectional"))
      (node (ref "U3") (pin "P$10") (pinfunction "VIN_P$10") (pintype "input"))
      (node (ref "U3") (pin "P$9") (pinfunction "VIN_P$9") (pintype "input"))
      (node (ref "U5") (pin "P$10") (pinfunction "VIN_P$10") (pintype "input"))
      (node (ref "U5") (pin "P$9") (pinfunction "VIN_P$9") (pintype "input"))
      (node (ref "U7") (pin "P$10") (pinfunction "VIN_P$10") (pintype "input"))
      (node (ref "U7") (pin "P$9") (pinfunction "VIN_P$9") (pintype "input"))
      (node (ref "U8") (pin "P$10") (pinfunction "VIN_P$10") (pintype "input"))
      (node (ref "U8") (pin "P$9") (pinfunction "VIN_P$9") (pintype "input"))
      (node (ref "U9") (pin "P$10") (pinfunction "VIN_P$10") (pintype "input"))
      (node (ref "U9") (pin "P$9") (pinfunction "VIN_P$9") (pintype "input"))
    )
    (net (code "118") (name "V_BATT_SENSE") (class "Default")
      (node (ref "R46") (pin "2") (pinfunction "2_2") (pintype "passive"))
      (node (ref "R47") (pin "2") (pinfunction "2_2") (pintype "passive"))
      (node (ref "U1") (pin "P$5") (pinfunction "P$5_P$5") (pintype "bidirectional"))
    )
    (net (code "119") (name "V_BUS") (class "Default")
      (node (ref "C25") (pin "1") (pinfunction "1_1") (pintype "passive"))
      (node (ref "C35") (pin "1") (pinfunction "1_1") (pintype "passive"))
      (node (ref "J14") (pin "1") (pinfunction "1_1") (pintype "bidirectional"))
      (node (ref "J16") (pin "1") (pinfunction "1_1") (pintype "bidirectional"))
      (node (ref "U4") (pin "P$10") (pinfunction "VIN_P$10") (pintype "input"))
      (node (ref "U4") (pin "P$11") (pinfunction "EN_P$11") (pintype "input"))
      (node (ref "U4") (pin "P$9") (pinfunction "VIN_P$9") (pintype "input"))
      (node (ref "U6") (pin "P$10") (pinfunction "VIN_P$10") (pintype "input"))
      (node (ref "U6") (pin "P$11") (pinfunction "EN_P$11") (pintype "input"))
      (node (ref "U6") (pin "P$9") (pinfunction "VIN_P$9") (pintype "input"))
    )
    (net (code "120") (name "unconnected-(H1-Pad1.2)") (class "Default")
      (node (ref "H1") (pin "1.2") (pinfunction "1.2_1.2") (pintype "bidirectional"))
    )
    (net (code "121") (name "unconnected-(H1-Pad1.4)") (class "Default")
      (node (ref "H1") (pin "1.4") (pinfunction "1.4_1.4") (pintype "bidirectional"))
    )
    (net (code "122") (name "unconnected-(H1-Pad1.5)") (class "Default")
      (node (ref "H1") (pin "1.5") (pinfunction "1.5_1.5") (pintype "bidirectional"))
    )
    (net (code "123") (name "unconnected-(H1-Pad1.6)") (class "Default")
      (node (ref "H1") (pin "1.6") (pinfunction "1.6_1.6") (pintype "bidirectional"))
    )
    (net (code "124") (name "unconnected-(H1-Pad1.7)") (class "Default")
      (node (ref "H1") (pin "1.7") (pinfunction "1.7_1.7") (pintype "bidirectional"))
    )
    (net (code "125") (name "unconnected-(H1-Pad1.8)") (class "Default")
      (node (ref "H1") (pin "1.8") (pinfunction "1.8_1.8") (pintype "bidirectional"))
    )
    (net (code "126") (name "unconnected-(H1-Pad1.9)") (class "Default")
      (node (ref "H1") (pin "1.9") (pinfunction "1.9_1.9") (pintype "bidirectional"))
    )
    (net (code "127") (name "unconnected-(H1-Pad1.11)") (class "Default")
      (node (ref "H1") (pin "1.11") (pinfunction "1.11_1.11") (pintype "bidirectional"))
    )
    (net (code "128") (name "unconnected-(H1-Pad1.12)") (class "Default")
      (node (ref "H1") (pin "1.12") (pinfunction "1.12_1.12") (pintype "bidirectional"))
    )
    (net (code "129") (name "unconnected-(H1-Pad1.13)") (class "Default")
      (node (ref "H1") (pin "1.13") (pinfunction "1.13_1.13") (pintype "bidirectional"))
    )
    (net (code "130") (name "unconnected-(H1-Pad1.14)") (class "Default")
      (node (ref "H1") (pin "1.14") (pinfunction "1.14_1.14") (pintype "bidirectional"))
    )
    (net (code "131") (name "unconnected-(H1-Pad1.15)") (class "Default")
      (node (ref "H1") (pin "1.15") (pinfunction "1.15_1.15") (pintype "bidirectional"))
    )
    (net (code "132") (name "unconnected-(H1-Pad1.16)") (class "Default")
      (node (ref "H1") (pin "1.16") (pinfunction "1.16_1.16") (pintype "bidirectional"))
    )
    (net (code "133") (name "unconnected-(H1-Pad1.17)") (class "Default")
      (node (ref "H1") (pin "1.17") (pinfunction "1.17_1.17") (pintype "bidirectional"))
    )
    (net (code "134") (name "unconnected-(H1-Pad1.18)") (class "Default")
      (node (ref "H1") (pin "1.18") (pinfunction "1.18_1.18") (pintype "bidirectional"))
    )
    (net (code "135") (name "unconnected-(H1-Pad1.19)") (class "Default")
      (node (ref "H1") (pin "1.19") (pinfunction "1.19_1.19") (pintype "bidirectional"))
    )
    (net (code "136") (name "unconnected-(H1-Pad1.20)") (class "Default")
      (node (ref "H1") (pin "1.20") (pinfunction "1.20_1.20") (pintype "bidirectional"))
    )
    (net (code "137") (name "unconnected-(H1-Pad1.21)") (class "Default")
      (node (ref "H1") (pin "1.21") (pinfunction "1.21_1.21") (pintype "bidirectional"))
    )
    (net (code "138") (name "unconnected-(H1-Pad1.22)") (class "Default")
      (node (ref "H1") (pin "1.22") (pinfunction "1.22_1.22") (pintype "bidirectional"))
    )
    (net (code "139") (name "unconnected-(H1-Pad1.23)") (class "Default")
      (node (ref "H1") (pin "1.23") (pinfunction "1.23_1.23") (pintype "bidirectional"))
    )
    (net (code "140") (name "unconnected-(H1-Pad1.24)") (class "Default")
      (node (ref "H1") (pin "1.24") (pinfunction "1.24_1.24") (pintype "bidirectional"))
    )
    (net (code "141") (name "unconnected-(H1-Pad1.25)") (class "Default")
      (node (ref "H1") (pin "1.25") (pinfunction "1.25_1.25") (pintype "bidirectional"))
    )
    (net (code "142") (name "unconnected-(H1-Pad1.26)") (class "Default")
      (node (ref "H1") (pin "1.26") (pinfunction "1.26_1.26") (pintype "bidirectional"))
    )
    (net (code "143") (name "unconnected-(H1-Pad1.27)") (class "Default")
      (node (ref "H1") (pin "1.27") (pinfunction "1.27_1.27") (pintype "bidirectional"))
    )
    (net (code "144") (name "unconnected-(H1-Pad1.28)") (class "Default")
      (node (ref "H1") (pin "1.28") (pinfunction "1.28_1.28") (pintype "bidirectional"))
    )
    (net (code "145") (name "unconnected-(H1-Pad1.29)") (class "Default")
      (node (ref "H1") (pin "1.29") (pinfunction "1.29_1.29") (pintype "bidirectional"))
    )
    (net (code "146") (name "unconnected-(H1-Pad1.30)") (class "Default")
      (node (ref "H1") (pin "1.30") (pinfunction "1.30_1.30") (pintype "bidirectional"))
    )
    (net (code "147") (name "unconnected-(H1-Pad1.31)") (class "Default")
      (node (ref "H1") (pin "1.31") (pinfunction "1.31_1.31") (pintype "bidirectional"))
    )
    (net (code "148") (name "unconnected-(H1-Pad1.32)") (class "Default")
      (node (ref "H1") (pin "1.32") (pinfunction "1.32_1.32") (pintype "bidirectional"))
    )
    (net (code "149") (name "unconnected-(H1-Pad1.33)") (class "Default")
      (node (ref "H1") (pin "1.33") (pinfunction "1.33_1.33") (pintype "bidirectional"))
    )
    (net (code "150") (name "unconnected-(H1-Pad1.34)") (class "Default")
      (node (ref "H1") (pin "1.34") (pinfunction "1.34_1.34") (pintype "bidirectional"))
    )
    (net (code "151") (name "unconnected-(H1-Pad1.35)") (class "Default")
      (node (ref "H1") (pin "1.35") (pinfunction "1.35_1.35") (pintype "bidirectional"))
    )
    (net (code "152") (name "unconnected-(H1-Pad1.36)") (class "Default")
      (node (ref "H1") (pin "1.36") (pinfunction "1.36_1.36") (pintype "bidirectional"))
    )
    (net (code "153") (name "unconnected-(H1-Pad1.37)") (class "Default")
      (node (ref "H1") (pin "1.37") (pinfunction "1.37_1.37") (pintype "bidirectional"))
    )
    (net (code "154") (name "unconnected-(H1-Pad1.38)") (class "Default")
      (node (ref "H1") (pin "1.38") (pinfunction "1.38_1.38") (pintype "bidirectional"))
    )
    (net (code "155") (name "unconnected-(H1-Pad1.39)") (class "Default")
      (node (ref "H1") (pin "1.39") (pinfunction "1.39_1.39") (pintype "bidirectional"))
    )
    (net (code "156") (name "unconnected-(H1-Pad1.40)") (class "Default")
      (node (ref "H1") (pin "1.40") (pinfunction "1.40_1.40") (pintype "bidirectional"))
    )
    (net (code "157") (name "unconnected-(H1-Pad1.42)") (class "Default")
      (node (ref "H1") (pin "1.42") (pinfunction "1.42_1.42") (pintype "bidirectional"))
    )
    (net (code "158") (name "unconnected-(H1-Pad1.44)") (class "Default")
      (node (ref "H1") (pin "1.44") (pinfunction "1.44_1.44") (pintype "bidirectional"))
    )
    (net (code "159") (name "unconnected-(H1-Pad1.46)") (class "Default")
      (node (ref "H1") (pin "1.46") (pinfunction "1.46_1.46") (pintype "bidirectional"))
    )
    (net (code "160") (name "unconnected-(H1-Pad1.47)") (class "Default")
      (node (ref "H1") (pin "1.47") (pinfunction "1.47_1.47") (pintype "bidirectional"))
    )
    (net (code "161") (name "unconnected-(H1-Pad2.2)") (class "Default")
      (node (ref "H1") (pin "2.2") (pinfunction "2.2_2.2") (pintype "bidirectional"))
    )
    (net (code "162") (name "unconnected-(H1-Pad2.4)") (class "Default")
      (node (ref "H1") (pin "2.4") (pinfunction "2.4_2.4") (pintype "bidirectional"))
    )
    (net (code "163") (name "unconnected-(H1-Pad2.5)") (class "Default")
      (node (ref "H1") (pin "2.5") (pinfunction "2.5_2.5") (pintype "bidirectional"))
    )
    (net (code "164") (name "unconnected-(H1-Pad2.6)") (class "Default")
      (node (ref "H1") (pin "2.6") (pinfunction "2.6_2.6") (pintype "bidirectional"))
    )
    (net (code "165") (name "unconnected-(H1-Pad2.7)") (class "Default")
      (node (ref "H1") (pin "2.7") (pinfunction "2.7_2.7") (pintype "bidirectional"))
    )
    (net (code "166") (name "unconnected-(H1-Pad2.8)") (class "Default")
      (node (ref "H1") (pin "2.8") (pinfunction "2.8_2.8") (pintype "bidirectional"))
    )
    (net (code "167") (name "unconnected-(H1-Pad2.10)") (class "Default")
      (node (ref "H1") (pin "2.10") (pinfunction "2.10_2.10") (pintype "bidirectional"))
    )
    (net (code "168") (name "unconnected-(H1-Pad2.11)") (class "Default")
      (node (ref "H1") (pin "2.11") (pinfunction "2.11_2.11") (pintype "bidirectional"))
    )
    (net (code "169") (name "unconnected-(H1-Pad2.12)") (class "Default")
      (node (ref "H1") (pin "2.12") (pinfunction "2.12_2.12") (pintype "bidirectional"))
    )
    (net (code "170") (name "unconnected-(H1-Pad2.15)") (class "Default")
      (node (ref "H1") (pin "2.15") (pinfunction "2.15_2.15") (pintype "bidirectional"))
    )
    (net (code "171") (name "unconnected-(H1-Pad2.35)") (class "Default")
      (node (ref "H1") (pin "2.35") (pinfunction "2.35_2.35") (pintype "bidirectional"))
    )
    (net (code "172") (name "unconnected-(H1-Pad2.36)") (class "Default")
      (node (ref "H1") (pin "2.36") (pinfunction "2.36_2.36") (pintype "bidirectional"))
    )
    (net (code "173") (name "unconnected-(H1-Pad2.37)") (class "Default")
      (node (ref "H1") (pin "2.37") (pinfunction "2.37_2.37") (pintype "bidirectional"))
    )
    (net (code "174") (name "unconnected-(H1-Pad2.38)") (class "Default")
      (node (ref "H1") (pin "2.38") (pinfunction "2.38_2.38") (pintype "bidirectional"))
    )
    (net (code "175") (name "unconnected-(H1-Pad2.39)") (class "Default")
      (node (ref "H1") (pin "2.39") (pinfunction "2.39_2.39") (pintype "bidirectional"))
    )
    (net (code "176") (name "unconnected-(H1-Pad2.40)") (class "Default")
      (node (ref "H1") (pin "2.40") (pinfunction "2.40_2.40") (pintype "bidirectional"))
    )
    (net (code "177") (name "unconnected-(H1-Pad2.41)") (class "Default")
      (node (ref "H1") (pin "2.41") (pinfunction "2.41_2.41") (pintype "bidirectional"))
    )
    (net (code "178") (name "unconnected-(H1-Pad2.42)") (class "Default")
      (node (ref "H1") (pin "2.42") (pinfunction "2.42_2.42") (pintype "bidirectional"))
    )
    (net (code "179") (name "unconnected-(H1-Pad2.43)") (class "Default")
      (node (ref "H1") (pin "2.43") (pinfunction "2.43_2.43") (pintype "bidirectional"))
    )
    (net (code "180") (name "unconnected-(H1-Pad2.44)") (class "Default")
      (node (ref "H1") (pin "2.44") (pinfunction "2.44_2.44") (pintype "bidirectional"))
    )
    (net (code "181") (name "unconnected-(H1-Pad2.50)") (class "Default")
      (node (ref "H1") (pin "2.50") (pinfunction "2.50_2.50") (pintype "bidirectional"))
    )
    (net (code "182") (name "unconnected-(H1-PadP$1)") (class "Default")
      (node (ref "H1") (pin "P$1") (pinfunction "P$1_P$1") (pintype "bidirectional"))
    )
    (net (code "183") (name "unconnected-(H1-PadP$2)") (class "Default")
      (node (ref "H1") (pin "P$2") (pinfunction "P$2_P$2") (pintype "bidirectional"))
    )
    (net (code "184") (name "unconnected-(H1-PadP$3)") (class "Default")
      (node (ref "H1") (pin "P$3") (pinfunction "P$3_P$3") (pintype "bidirectional"))
    )
    (net (code "185") (name "unconnected-(J6-PadD+)") (class "Default")
      (node (ref "J6") (pin "D+") (pinfunction "D+_D+") (pintype "bidirectional"))
    )
    (net (code "186") (name "unconnected-(J6-PadD-)") (class "Default")
      (node (ref "J6") (pin "D-") (pinfunction "D-_D-") (pintype "bidirectional"))
    )
    (net (code "187") (name "unconnected-(J6-PadID)") (class "Default")
      (node (ref "J6") (pin "ID") (pinfunction "ID_ID") (pintype "bidirectional"))
    )
    (net (code "188") (name "unconnected-(U1-PadP$2)") (class "Default")
      (node (ref "U1") (pin "P$2") (pinfunction "P$2_P$2") (pintype "bidirectional"))
    )
    (net (code "189") (name "unconnected-(U1-PadP$12)") (class "Default")
      (node (ref "U1") (pin "P$12") (pinfunction "P$12_P$12") (pintype "bidirectional"))
    )
    (net (code "190") (name "unconnected-(U1-PadP$13)") (class "Default")
      (node (ref "U1") (pin "P$13") (pinfunction "P$13_P$13") (pintype "bidirectional"))
    )
    (net (code "191") (name "unconnected-(U2-ISMON-PadP$13)") (class "Default")
      (node (ref "U2") (pin "P$13") (pinfunction "ISMON_P$13") (pintype "bidirectional"))
    )
    (net (code "192") (name "unconnected-(U2-LOADTG-PadP$20)") (class "Default")
      (node (ref "U2") (pin "P$20") (pinfunction "LOADTG_P$20") (pintype "bidirectional"))
    )
    (net (code "193") (name "unconnected-(U3-SYNC-PadP$16)") (class "Default")
      (node (ref "U3") (pin "P$16") (pinfunction "SYNC_P$16") (pintype "input"))
    )
    (net (code "194") (name "unconnected-(U4-SYNC-PadP$16)") (class "Default")
      (node (ref "U4") (pin "P$16") (pinfunction "SYNC_P$16") (pintype "input"))
    )
    (net (code "195") (name "unconnected-(U5-SYNC-PadP$16)") (class "Default")
      (node (ref "U5") (pin "P$16") (pinfunction "SYNC_P$16") (pintype "input"))
    )
    (net (code "196") (name "unconnected-(U6-SYNC-PadP$16)") (class "Default")
      (node (ref "U6") (pin "P$16") (pinfunction "SYNC_P$16") (pintype "input"))
    )
    (net (code "197") (name "unconnected-(U7-SYNC-PadP$16)") (class "Default")
      (node (ref "U7") (pin "P$16") (pinfunction "SYNC_P$16") (pintype "input"))
    )
    (net (code "198") (name "unconnected-(U8-SYNC-PadP$16)") (class "Default")
      (node (ref "U8") (pin "P$16") (pinfunction "SYNC_P$16") (pintype "input"))
    )
    (net (code "199") (name "unconnected-(U9-SYNC-PadP$16)") (class "Default")
      (node (ref "U9") (pin "P$16") (pinfunction "SYNC_P$16") (pintype "input"))
    )
    (net (code "200") (name "unconnected-(U10-SYNC-PadP$16)") (class "Default")
      (node (ref "U10") (pin "P$16") (pinfunction "SYNC_P$16") (pintype "input"))
    )
  )
)
